# kulgurpowerMCU2.net
KiCad netlist of a schematic drawn in EAGLE
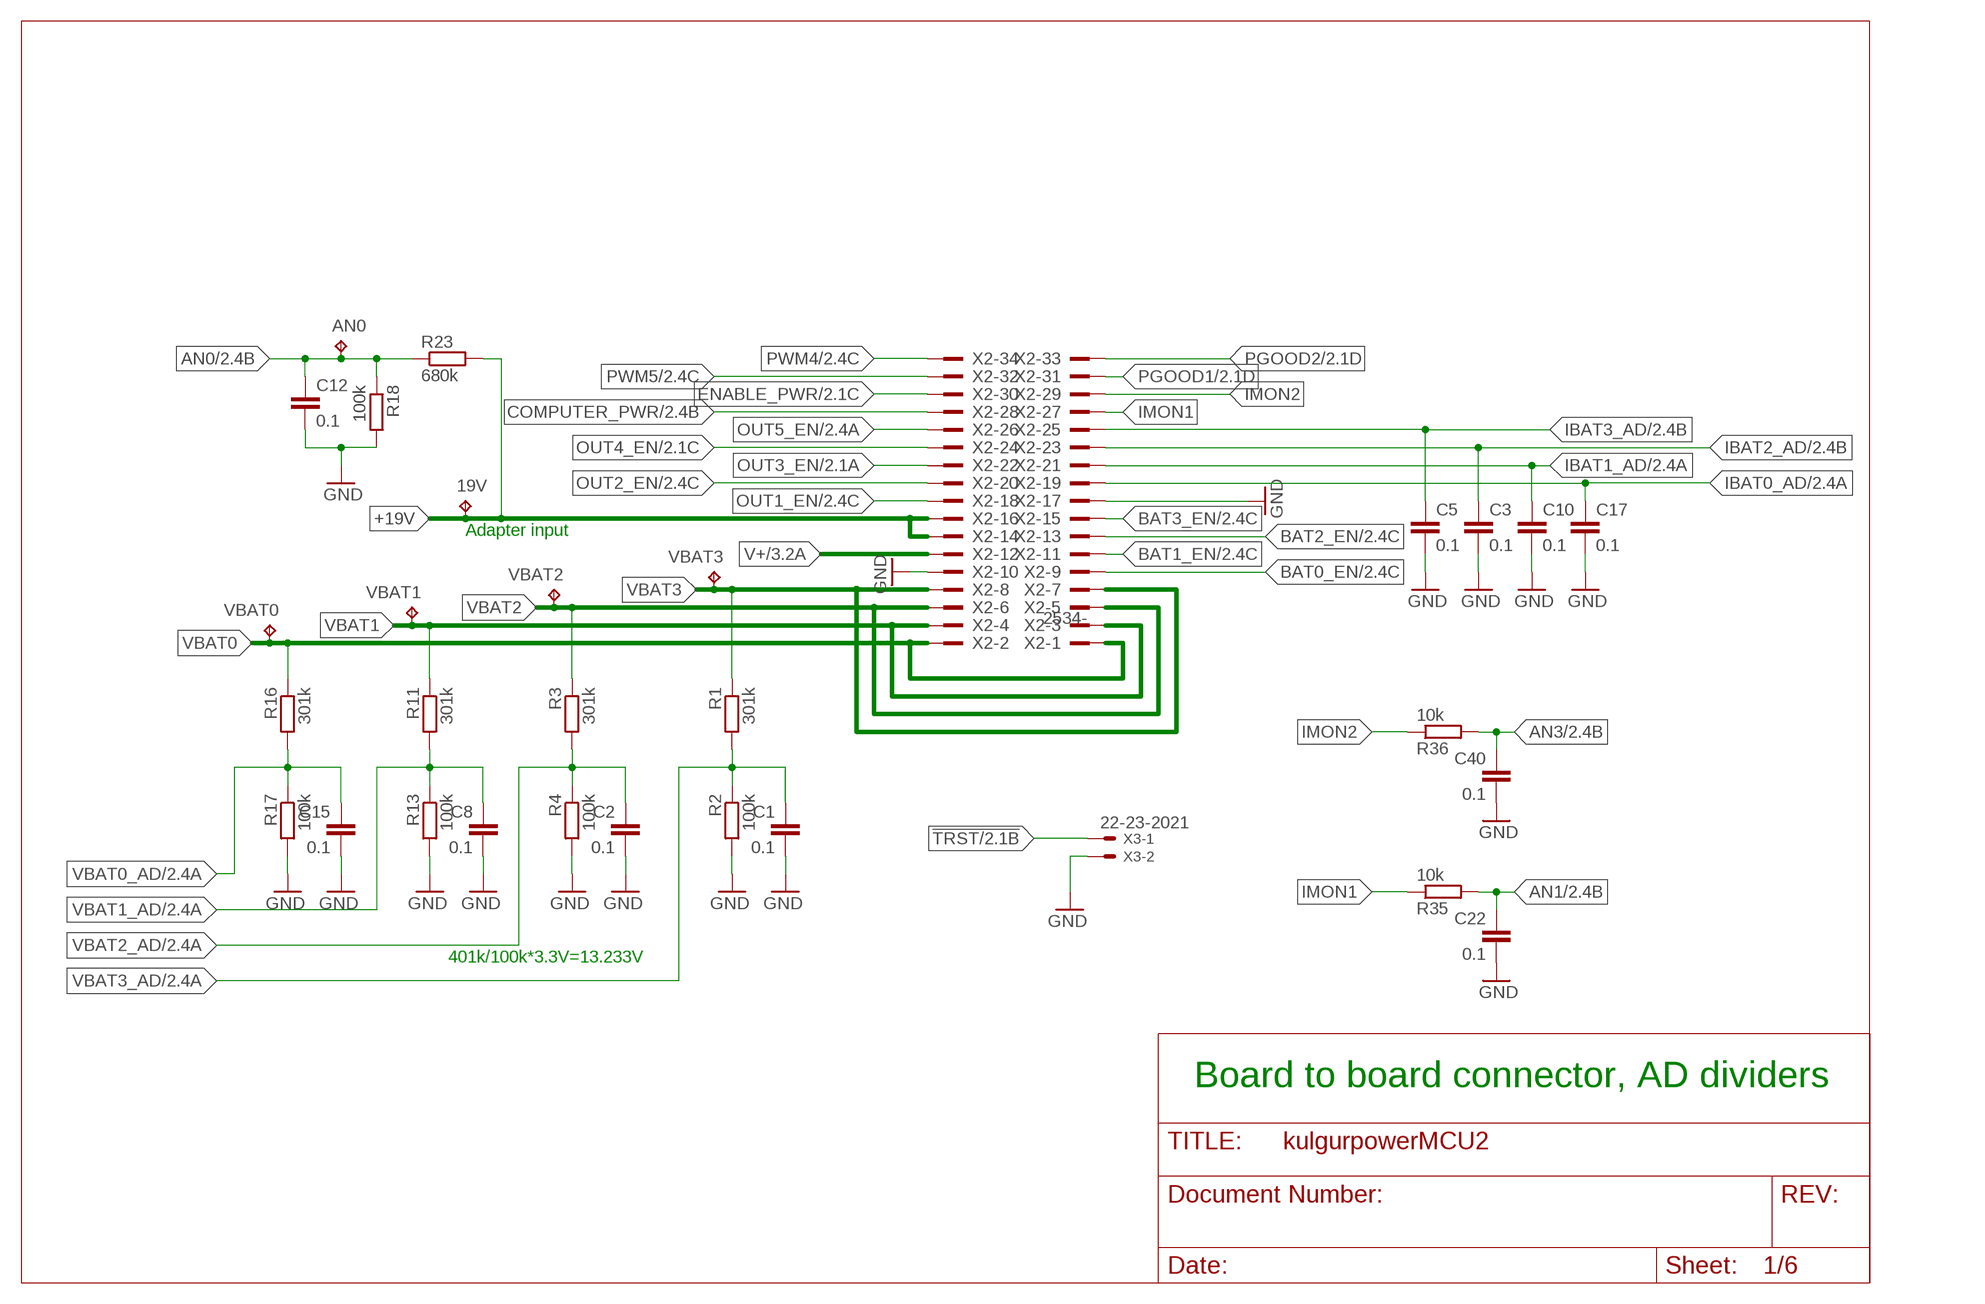
[diagram p0: schematic, sheet 1]
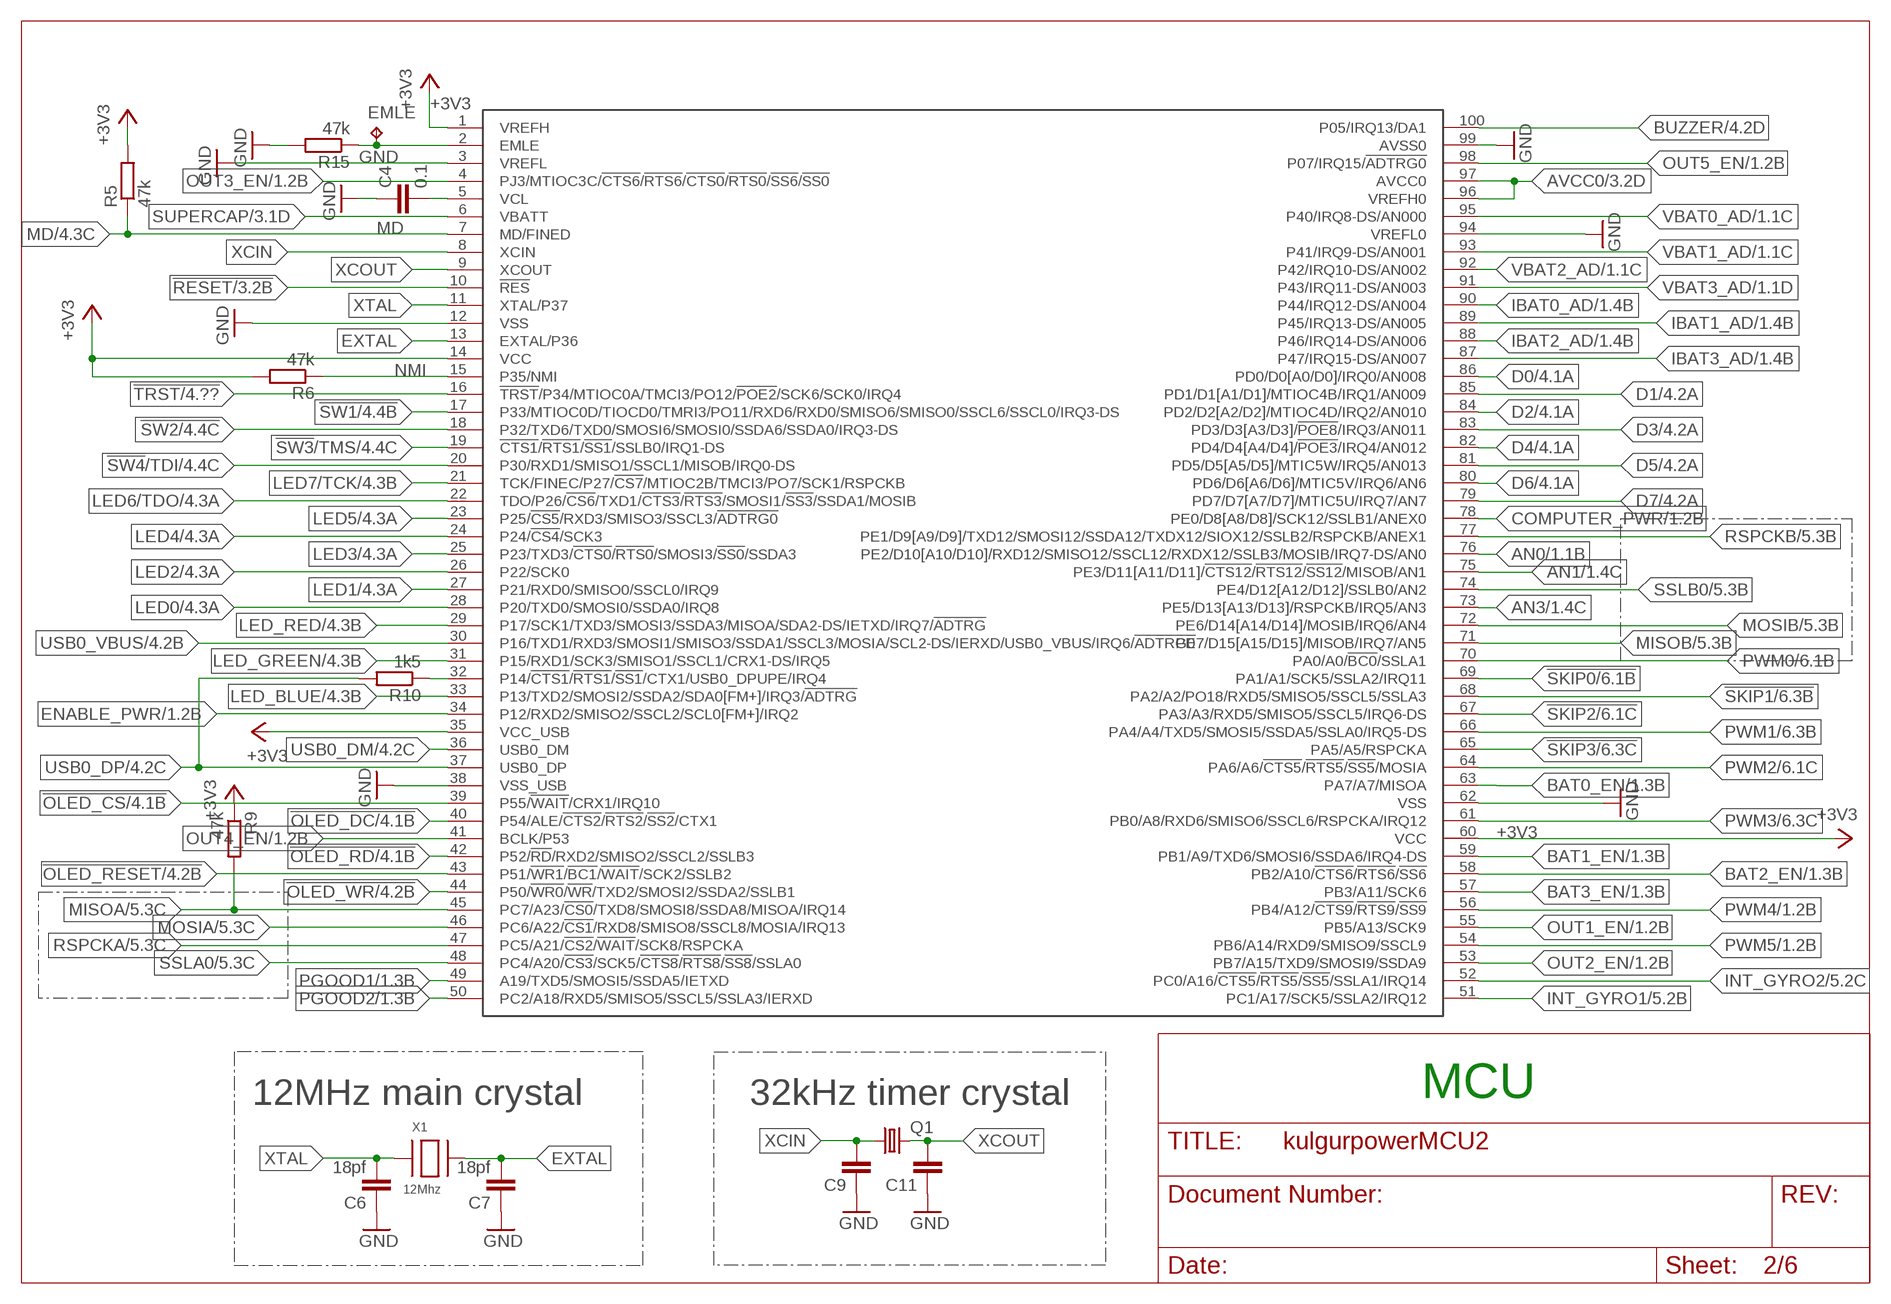
[diagram p1: schematic, sheet 2]
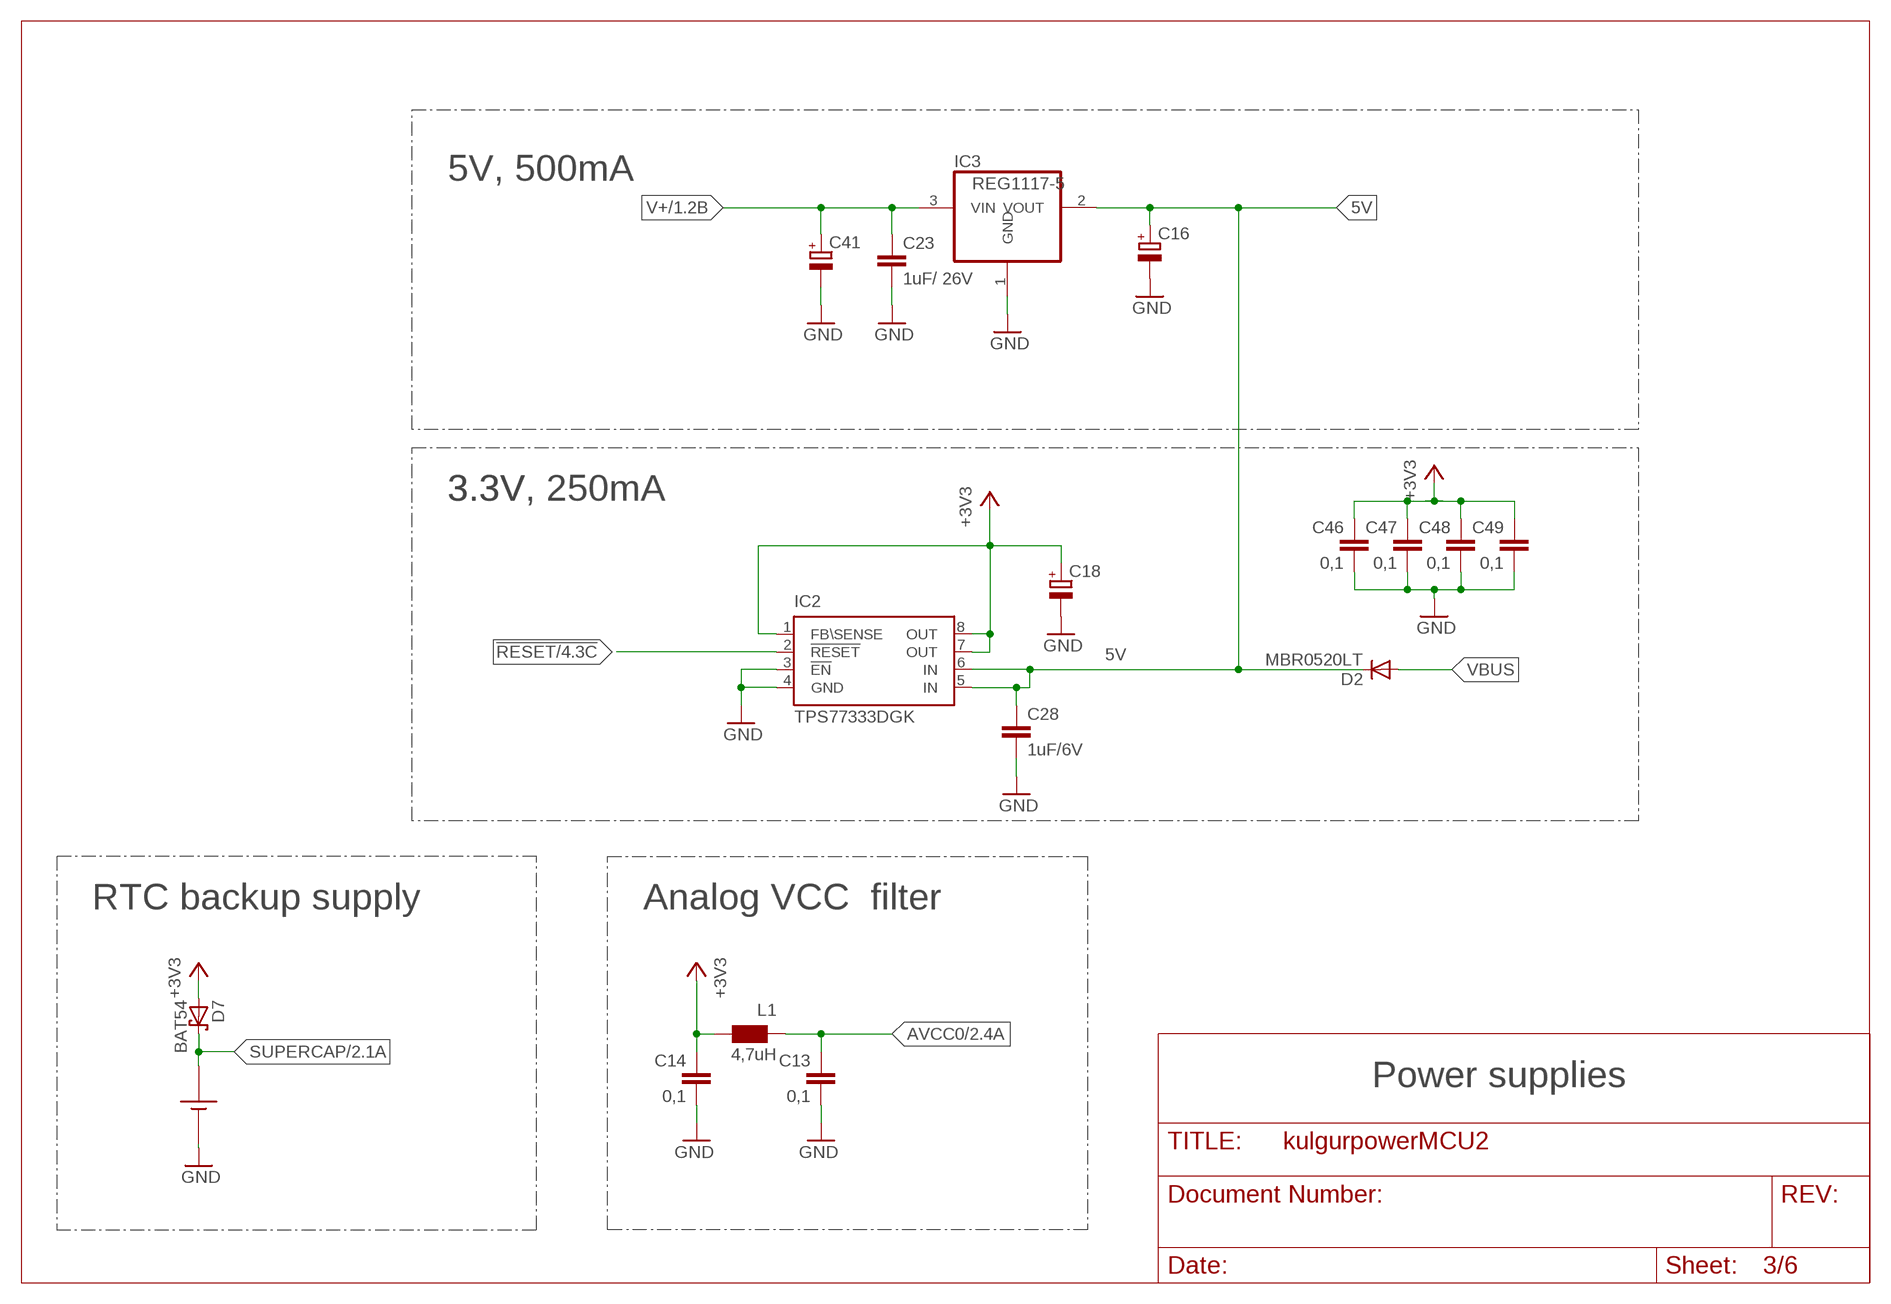
[diagram p2: schematic, sheet 3]
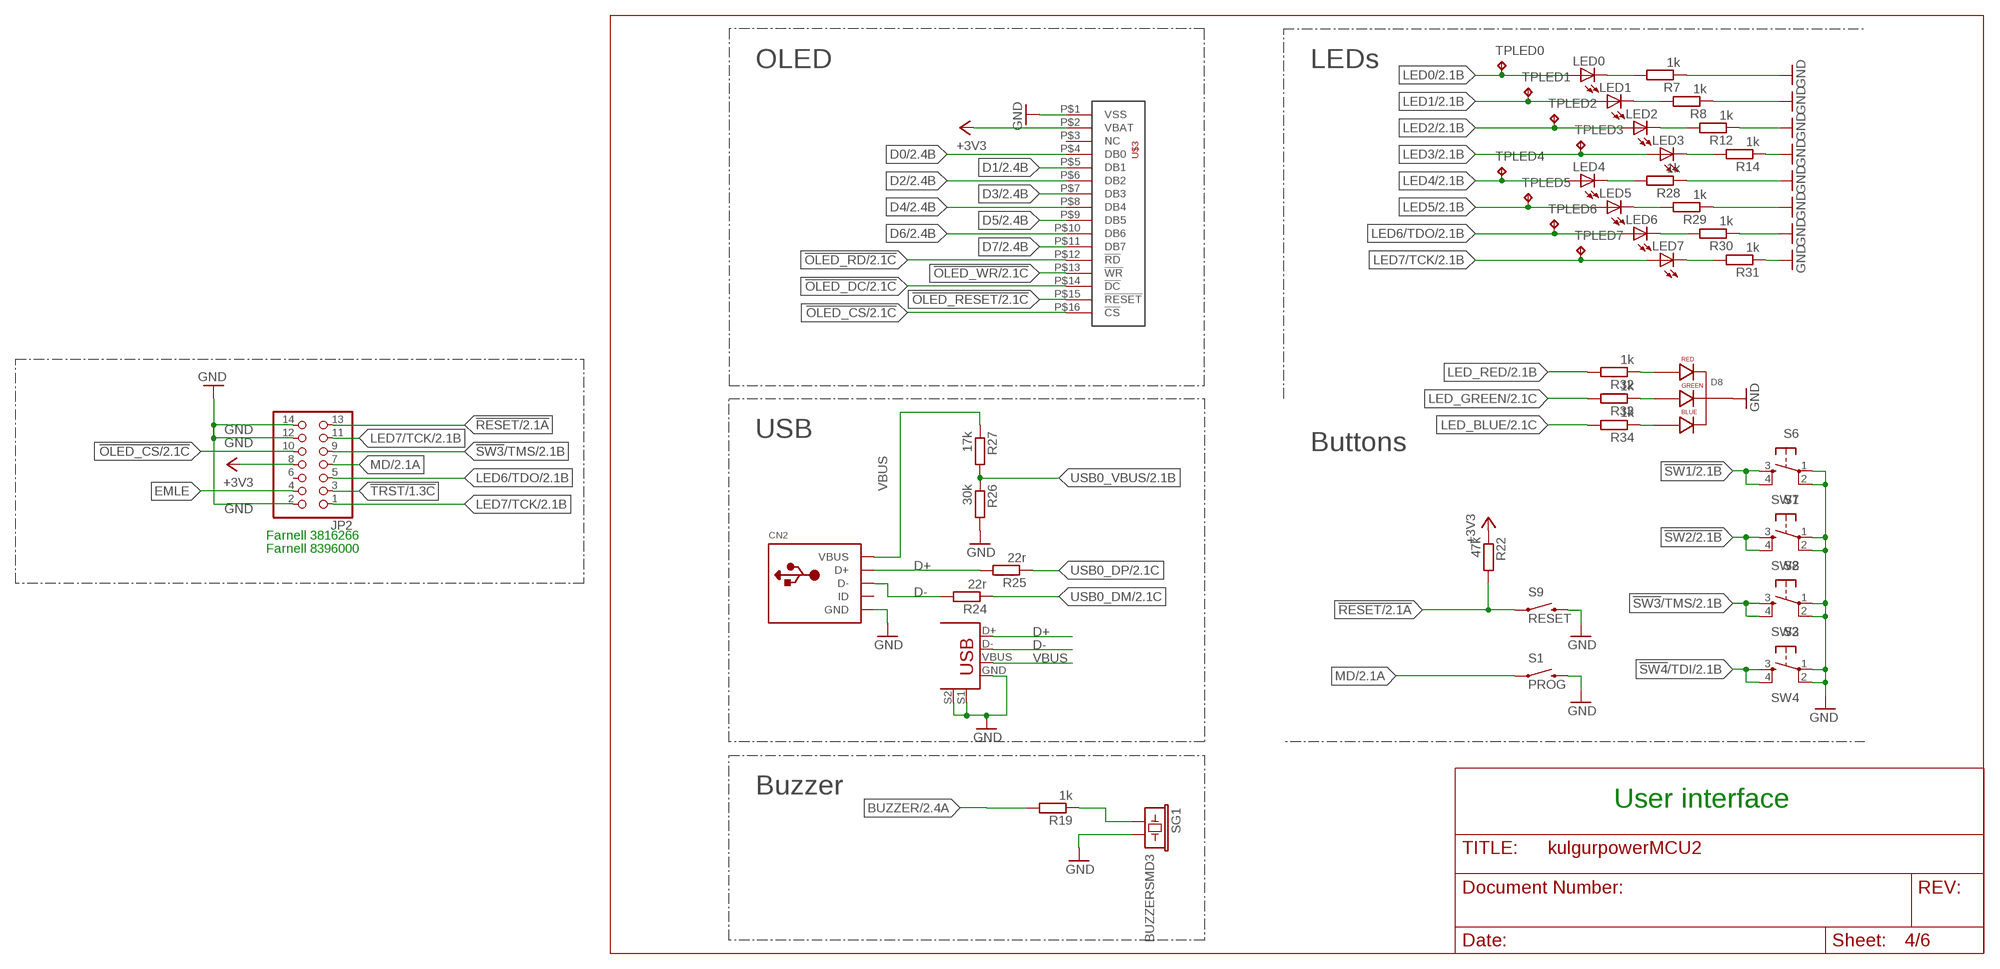
[diagram p3: schematic, sheet 4]
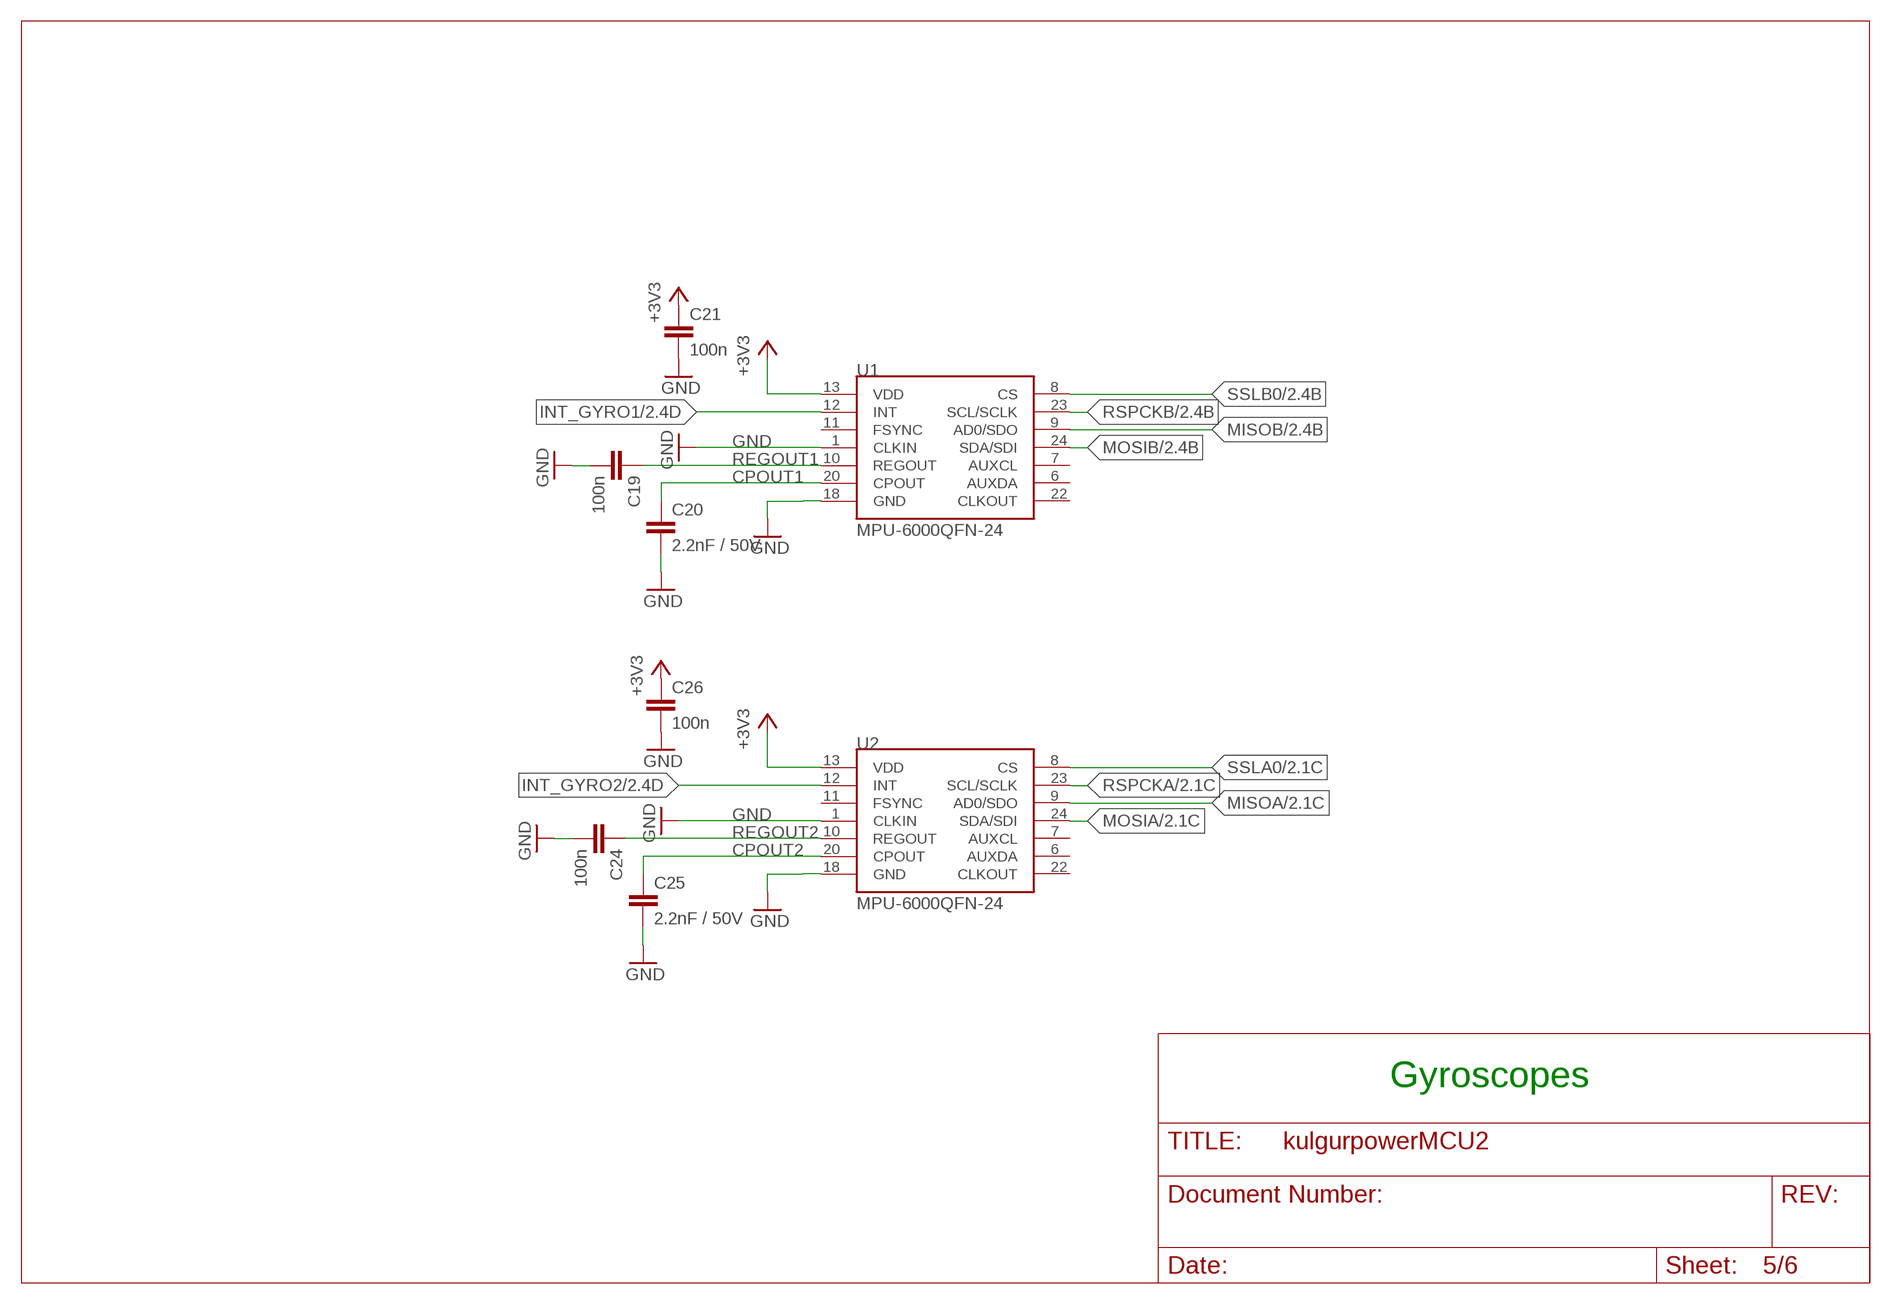
[diagram p4: schematic, sheet 5]
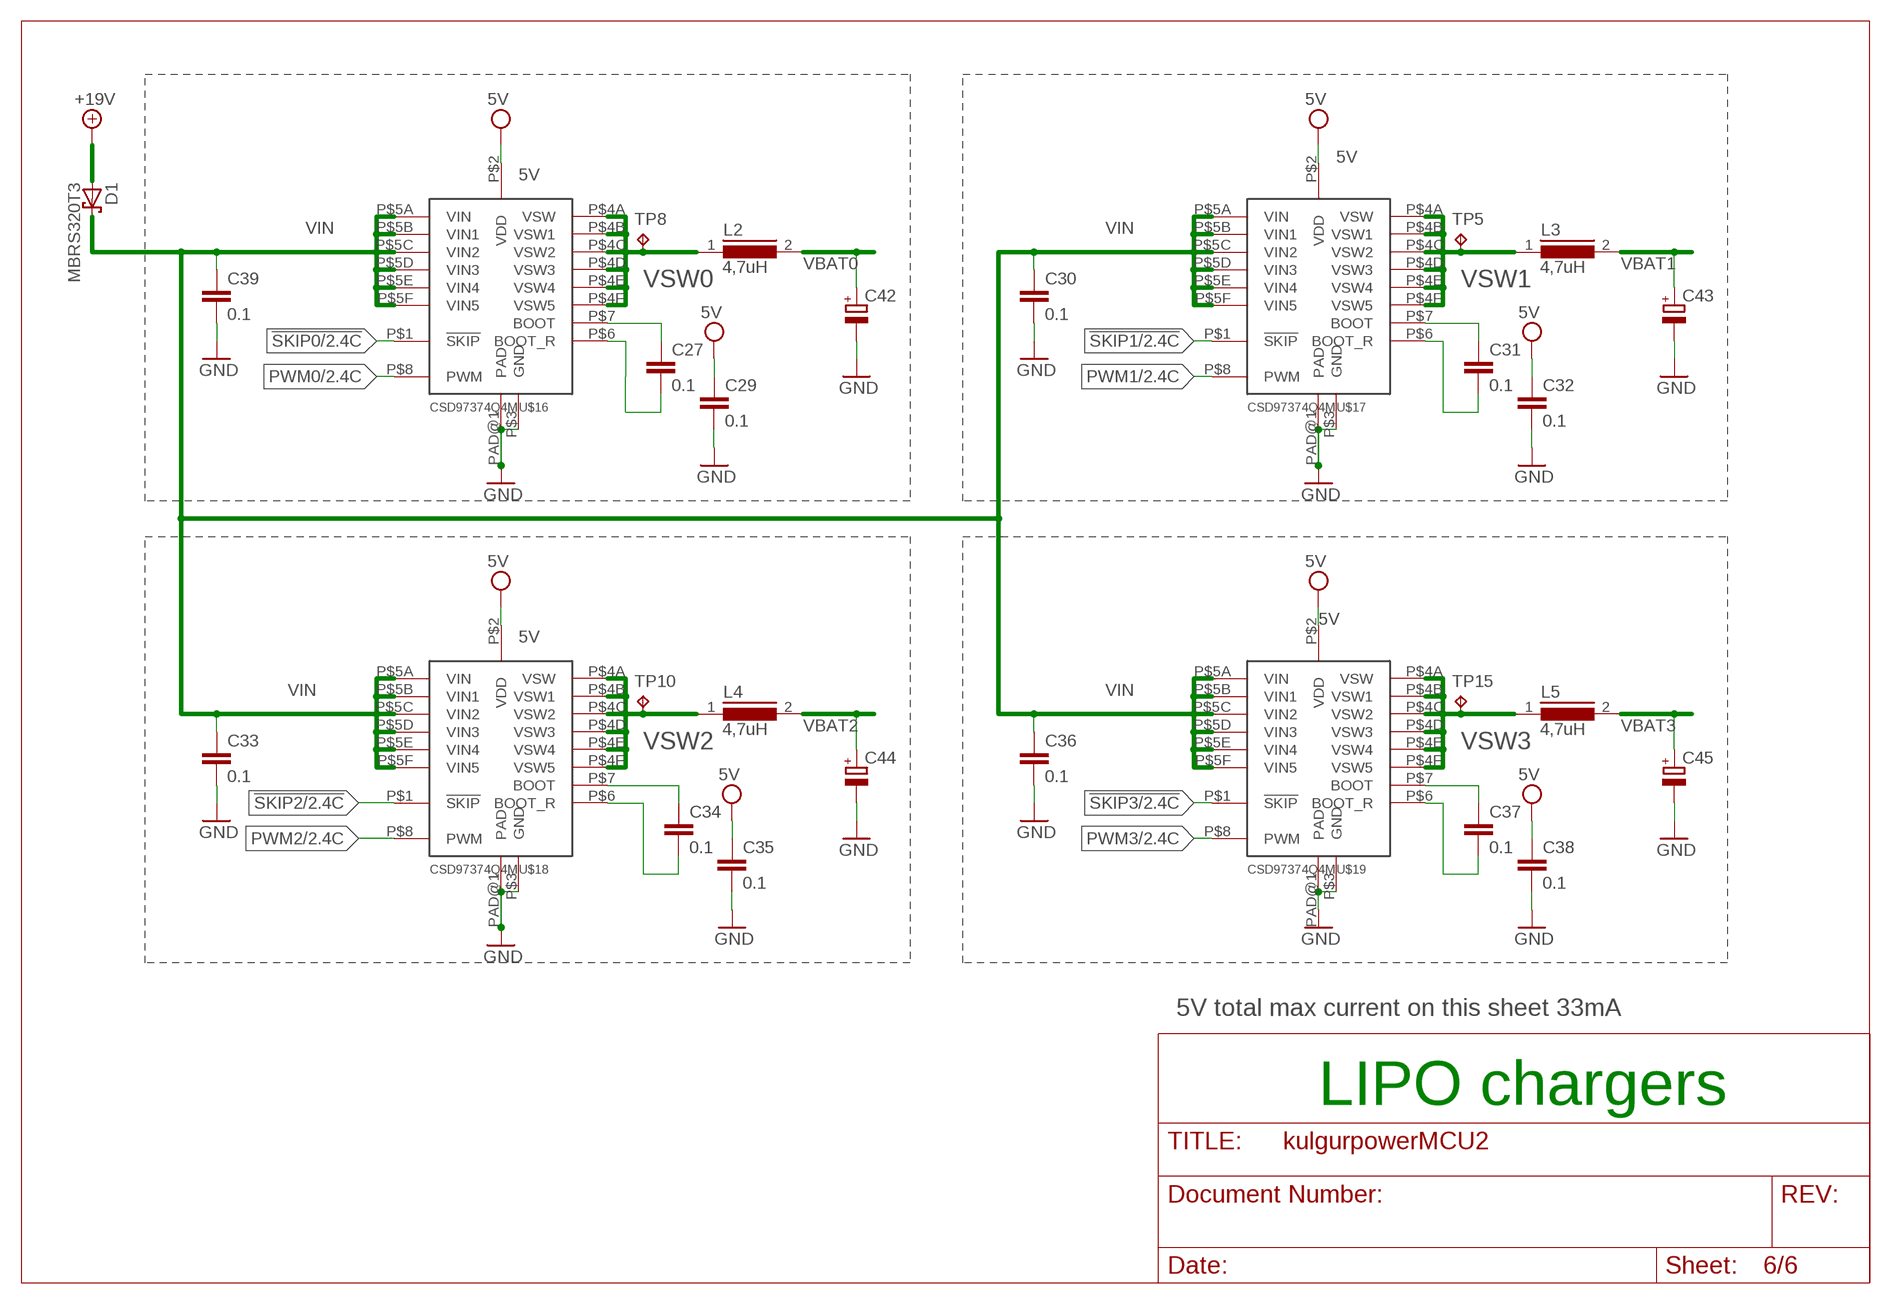
[diagram p5: schematic, sheet 6]

(export (version "E")
  (design (tool "Eeschema 10.0.6"))
  (components
    (comp (ref "C13")
      (value "0,1")
      (footprint "eagle-import:0603-CAP")
      (libsource (lib "eagle-import") (part "CAP0603-CAP"))
    )
    (comp (ref "C14")
      (value "0,1")
      (footprint "eagle-import:0603-CAP")
      (libsource (lib "eagle-import") (part "CAP0603-CAP"))
    )
    (comp (ref "C16")
      (value "CPOL-EUC/6032-28R")
      (footprint "eagle-import:C_6032-28R")
      (libsource (lib "eagle-import") (part "CPOL-EUC/6032-28R"))
    )
    (comp (ref "C18")
      (value "CPOL-EUC/6032-28R")
      (footprint "eagle-import:C_6032-28R")
      (libsource (lib "eagle-import") (part "CPOL-EUC/6032-28R"))
    )
    (comp (ref "C23")
      (value "1uF/ 26V")
      (footprint "eagle-import:C0805")
      (libsource (lib "eagle-import") (part "resistor_C-EUC0805"))
    )
    (comp (ref "C28")
      (value "1uF/6V")
      (footprint "eagle-import:C0603")
      (libsource (lib "eagle-import") (part "resistor_C-EUC0603"))
    )
    (comp (ref "C41")
      (value "CPOL-EUC/6032-28R")
      (footprint "eagle-import:C_6032-28R")
      (libsource (lib "eagle-import") (part "CPOL-EUC/6032-28R"))
    )
    (comp (ref "C46")
      (value "0,1")
      (footprint "eagle-import:0603-CAP")
      (libsource (lib "eagle-import") (part "CAP0603-CAP"))
    )
    (comp (ref "C47")
      (value "0,1")
      (footprint "eagle-import:0603-CAP")
      (libsource (lib "eagle-import") (part "CAP0603-CAP"))
    )
    (comp (ref "C48")
      (value "0,1")
      (footprint "eagle-import:0603-CAP")
      (libsource (lib "eagle-import") (part "CAP0603-CAP"))
    )
    (comp (ref "C49")
      (value "0,1")
      (footprint "eagle-import:0603-CAP")
      (libsource (lib "eagle-import") (part "CAP0603-CAP"))
    )
    (comp (ref "D2")
      (value "MBR0520LT")
      (footprint "eagle-import:SOD123")
      (libsource (lib "eagle-import") (part "MBR0520LT"))
    )
    (comp (ref "D7")
      (value "BAT54")
      (footprint "eagle-import:SOT23")
      (libsource (lib "eagle-import") (part "BAT54"))
    )
    (comp (ref "IC2")
      (value "TPS77333DGK")
      (footprint "eagle-import:MSOP8")
      (libsource (lib "eagle-import") (part "TPS773"))
    )
    (comp (ref "IC3")
      (value "REG1117-5")
      (footprint "eagle-import:SOT223")
      (fields (field (name "MPN") "REG1117"))
      (libsource (lib "eagle-import") (part "REG1117"))
    )
    (comp (ref "L1")
      (value "4,7uH")
      (footprint "eagle-import:WE-KI_0805_B")
      (libsource (lib "eagle-import") (part "WE-KIHQ_0805"))
    )
    (comp (ref "U$1")
      (value "EDLRD224V3R6C")
      (footprint "eagle-import:EDLRD224V3R6C")
      (libsource (lib "eagle-import") (part "EDLRD224V3R6C"))
    )
    (comp (ref "C19")
      (value "100n")
      (footprint "eagle-import:C0603")
      (libsource (lib "eagle-import") (part "C-EUC0603"))
    )
    (comp (ref "C20")
      (value "2.2nF / 50V")
      (footprint "eagle-import:C0402")
      (libsource (lib "eagle-import") (part "C0402"))
    )
    (comp (ref "C21")
      (value "100n")
      (footprint "eagle-import:C0603")
      (libsource (lib "eagle-import") (part "C-EUC0603"))
    )
    (comp (ref "C24")
      (value "100n")
      (footprint "eagle-import:C0603")
      (libsource (lib "eagle-import") (part "C-EUC0603"))
    )
    (comp (ref "C25")
      (value "2.2nF / 50V")
      (footprint "eagle-import:C0402")
      (libsource (lib "eagle-import") (part "C0402"))
    )
    (comp (ref "C26")
      (value "100n")
      (footprint "eagle-import:C0603")
      (libsource (lib "eagle-import") (part "C-EUC0603"))
    )
    (comp (ref "U1")
      (value "MPU-6000QFN-24")
      (footprint "eagle-import:QFN-24-TESTING")
      (libsource (lib "eagle-import") (part "MPU-6000QFN-24"))
    )
    (comp (ref "U2")
      (value "MPU-6000QFN-24")
      (footprint "eagle-import:QFN-24-TESTING")
      (libsource (lib "eagle-import") (part "MPU-6000QFN-24"))
    )
    (comp (ref "CN2")
      (value "USBMINIB")
      (footprint "eagle-import:USB-MINIB")
      (libsource (lib "eagle-import") (part "USBMINIB"))
    )
    (comp (ref "D8")
      (value "WP154A4SUREQBFZGW")
      (footprint "eagle-import:LED-RGB-THRU")
      (fields (field (name "PROD_ID") "DIO-09434"))
      (libsource (lib "eagle-import") (part "LED-RGB-CC-THRUDIFFUSE"))
    )
    (comp (ref "JP2")
      (value "PINHD-2X7")
      (footprint "eagle-import:2X07")
      (libsource (lib "eagle-import") (part "PINHD-2X7"))
    )
    (comp (ref "LED0")
      (value "LED0603")
      (footprint "eagle-import:LED-0603")
      (libsource (lib "eagle-import") (part "LED0603"))
    )
    (comp (ref "LED1")
      (value "LED0603")
      (footprint "eagle-import:LED-0603")
      (libsource (lib "eagle-import") (part "LED0603"))
    )
    (comp (ref "LED2")
      (value "LED0603")
      (footprint "eagle-import:LED-0603")
      (libsource (lib "eagle-import") (part "LED0603"))
    )
    (comp (ref "LED3")
      (value "LED0603")
      (footprint "eagle-import:LED-0603")
      (libsource (lib "eagle-import") (part "LED0603"))
    )
    (comp (ref "LED4")
      (value "LED0603")
      (footprint "eagle-import:LED-0603")
      (libsource (lib "eagle-import") (part "LED0603"))
    )
    (comp (ref "LED5")
      (value "LED0603")
      (footprint "eagle-import:LED-0603")
      (libsource (lib "eagle-import") (part "LED0603"))
    )
    (comp (ref "LED6")
      (value "LED0603")
      (footprint "eagle-import:LED-0603")
      (libsource (lib "eagle-import") (part "LED0603"))
    )
    (comp (ref "LED7")
      (value "LED0603")
      (footprint "eagle-import:LED-0603")
      (libsource (lib "eagle-import") (part "LED0603"))
    )
    (comp (ref "R7")
      (value "1k")
      (footprint "eagle-import:R0603")
      (libsource (lib "eagle-import") (part "R-EU_R0603"))
    )
    (comp (ref "R8")
      (value "1k")
      (footprint "eagle-import:R0603")
      (libsource (lib "eagle-import") (part "R-EU_R0603"))
    )
    (comp (ref "R12")
      (value "1k")
      (footprint "eagle-import:R0603")
      (libsource (lib "eagle-import") (part "R-EU_R0603"))
    )
    (comp (ref "R14")
      (value "1k")
      (footprint "eagle-import:R0603")
      (libsource (lib "eagle-import") (part "R-EU_R0603"))
    )
    (comp (ref "R19")
      (value "1k")
      (footprint "eagle-import:R0603")
      (libsource (lib "eagle-import") (part "R-EU_R0603"))
    )
    (comp (ref "R22")
      (value "47k")
      (footprint "eagle-import:R0603")
      (libsource (lib "eagle-import") (part "R-EU_R0603"))
    )
    (comp (ref "R24")
      (value "22r")
      (footprint "eagle-import:R0603")
      (libsource (lib "eagle-import") (part "R-EU_R0603"))
    )
    (comp (ref "R25")
      (value "22r")
      (footprint "eagle-import:R0603")
      (libsource (lib "eagle-import") (part "R-EU_R0603"))
    )
    (comp (ref "R26")
      (value "30k")
      (footprint "eagle-import:R0603")
      (libsource (lib "eagle-import") (part "R-EU_R0603"))
    )
    (comp (ref "R27")
      (value "17k")
      (footprint "eagle-import:R0603")
      (libsource (lib "eagle-import") (part "R-EU_R0603"))
    )
    (comp (ref "R28")
      (value "1k")
      (footprint "eagle-import:R0603")
      (libsource (lib "eagle-import") (part "R-EU_R0603"))
    )
    (comp (ref "R29")
      (value "1k")
      (footprint "eagle-import:R0603")
      (libsource (lib "eagle-import") (part "R-EU_R0603"))
    )
    (comp (ref "R30")
      (value "1k")
      (footprint "eagle-import:R0603")
      (libsource (lib "eagle-import") (part "R-EU_R0603"))
    )
    (comp (ref "R31")
      (value "1k")
      (footprint "eagle-import:R0603")
      (libsource (lib "eagle-import") (part "R-EU_R0603"))
    )
    (comp (ref "R32")
      (value "1k")
      (footprint "eagle-import:R0603")
      (libsource (lib "eagle-import") (part "R-EU_R0603"))
    )
    (comp (ref "R33")
      (value "1k")
      (footprint "eagle-import:R0603")
      (libsource (lib "eagle-import") (part "R-EU_R0603"))
    )
    (comp (ref "R34")
      (value "1k")
      (footprint "eagle-import:R0603")
      (libsource (lib "eagle-import") (part "R-EU_R0603"))
    )
    (comp (ref "S1")
      (value "PROG")
      (footprint "eagle-import:TACTILE-PTH-SIDEEZ")
      (libsource (lib "eagle-import") (part "SWITCH-MOMENTARY-2SIDE_EZ"))
    )
    (comp (ref "S2")
      (value "SW4")
      (footprint "eagle-import:TACTILE_SWITCH_SMD")
      (fields (field (name "PROD_ID") "SWCH-08247"))
      (libsource (lib "eagle-import") (part "TAC_SWITCHSMD"))
    )
    (comp (ref "S6")
      (value "SW1")
      (footprint "eagle-import:TACTILE_SWITCH_SMD")
      (libsource (lib "eagle-import") (part "TAC_SWITCHSMD"))
    )
    (comp (ref "S7")
      (value "SW2")
      (footprint "eagle-import:TACTILE_SWITCH_SMD")
      (libsource (lib "eagle-import") (part "TAC_SWITCHSMD"))
    )
    (comp (ref "S8")
      (value "SW3")
      (footprint "eagle-import:TACTILE_SWITCH_SMD")
      (libsource (lib "eagle-import") (part "TAC_SWITCHSMD"))
    )
    (comp (ref "S9")
      (value "RESET")
      (footprint "eagle-import:TACTILE-PTH-SIDEEZ")
      (libsource (lib "eagle-import") (part "SWITCH-MOMENTARY-2SIDE_EZ"))
    )
    (comp (ref "SG1")
      (value "BUZZERSMD3")
      (footprint "eagle-import:BUZZER-CMT1102")
      (libsource (lib "eagle-import") (part "BUZZERSMD3"))
    )
    (comp (ref "TPLED0")
      (value "LED0")
      (footprint "eagle-import:B1,27")
      (libsource (lib "eagle-import") (part "TPB1,27"))
    )
    (comp (ref "TPLED1")
      (value "LED0")
      (footprint "eagle-import:B1,27")
      (libsource (lib "eagle-import") (part "TPB1,27"))
    )
    (comp (ref "TPLED2")
      (value "LED0")
      (footprint "eagle-import:B1,27")
      (libsource (lib "eagle-import") (part "TPB1,27"))
    )
    (comp (ref "TPLED3")
      (value "LED0")
      (footprint "eagle-import:B1,27")
      (libsource (lib "eagle-import") (part "TPB1,27"))
    )
    (comp (ref "TPLED4")
      (value "LED0")
      (footprint "eagle-import:B1,27")
      (libsource (lib "eagle-import") (part "TPB1,27"))
    )
    (comp (ref "TPLED5")
      (value "LED0")
      (footprint "eagle-import:B1,27")
      (libsource (lib "eagle-import") (part "TPB1,27"))
    )
    (comp (ref "TPLED6")
      (value "LED0")
      (footprint "eagle-import:B1,27")
      (libsource (lib "eagle-import") (part "TPB1,27"))
    )
    (comp (ref "TPLED7")
      (value "LED0")
      (footprint "eagle-import:B1,27")
      (libsource (lib "eagle-import") (part "TPB1,27"))
    )
    (comp (ref "U$2")
      (value "USB+SHIELD")
      (footprint "eagle-import:USB-B-PTH")
      (libsource (lib "eagle-import") (part "USB+SHIELD"))
    )
    (comp (ref "U$3")
      (value "ER-OLEDM032-1")
      (footprint "eagle-import:ER-OLEDM032-1")
      (libsource (lib "eagle-import") (part "ER-OLEDM032-1"))
    )
    (comp (ref "19V")
      (value "TPB1,27")
      (footprint "eagle-import:B1,27")
      (libsource (lib "eagle-import") (part "TPB1,27"))
    )
    (comp (ref "AN0")
      (value "TPB1,27")
      (footprint "eagle-import:B1,27")
      (libsource (lib "eagle-import") (part "TPB1,27"))
    )
    (comp (ref "C1")
      (value "0.1")
      (footprint "eagle-import:C0603")
      (libsource (lib "eagle-import") (part "C-EUC0603"))
    )
    (comp (ref "C2")
      (value "0.1")
      (footprint "eagle-import:C0603")
      (libsource (lib "eagle-import") (part "C-EUC0603"))
    )
    (comp (ref "C3")
      (value "0.1")
      (footprint "eagle-import:C0603")
      (libsource (lib "eagle-import") (part "C-EUC0603"))
    )
    (comp (ref "C5")
      (value "0.1")
      (footprint "eagle-import:C0603")
      (libsource (lib "eagle-import") (part "C-EUC0603"))
    )
    (comp (ref "C8")
      (value "0.1")
      (footprint "eagle-import:C0603")
      (libsource (lib "eagle-import") (part "C-EUC0603"))
    )
    (comp (ref "C10")
      (value "0.1")
      (footprint "eagle-import:C0603")
      (libsource (lib "eagle-import") (part "C-EUC0603"))
    )
    (comp (ref "C12")
      (value "0.1")
      (footprint "eagle-import:0603-CAP")
      (libsource (lib "eagle-import") (part "CAP0603-CAP"))
    )
    (comp (ref "C15")
      (value "0.1")
      (footprint "eagle-import:C0603")
      (libsource (lib "eagle-import") (part "C-EUC0603"))
    )
    (comp (ref "C17")
      (value "0.1")
      (footprint "eagle-import:C0603")
      (libsource (lib "eagle-import") (part "C-EUC0603"))
    )
    (comp (ref "C22")
      (value "0.1")
      (footprint "eagle-import:C0603")
      (libsource (lib "eagle-import") (part "C-EUC0603"))
    )
    (comp (ref "C40")
      (value "0.1")
      (footprint "eagle-import:C0603")
      (libsource (lib "eagle-import") (part "C-EUC0603"))
    )
    (comp (ref "R1")
      (value "301k")
      (footprint "eagle-import:R0603")
      (libsource (lib "eagle-import") (part "R-EU_R0603"))
    )
    (comp (ref "R2")
      (value "100k")
      (footprint "eagle-import:R0603")
      (libsource (lib "eagle-import") (part "R-EU_R0603"))
    )
    (comp (ref "R3")
      (value "301k")
      (footprint "eagle-import:R0603")
      (libsource (lib "eagle-import") (part "R-EU_R0603"))
    )
    (comp (ref "R4")
      (value "100k")
      (footprint "eagle-import:R0603")
      (libsource (lib "eagle-import") (part "R-EU_R0603"))
    )
    (comp (ref "R11")
      (value "301k")
      (footprint "eagle-import:R0603")
      (libsource (lib "eagle-import") (part "R-EU_R0603"))
    )
    (comp (ref "R13")
      (value "100k")
      (footprint "eagle-import:R0603")
      (libsource (lib "eagle-import") (part "R-EU_R0603"))
    )
    (comp (ref "R16")
      (value "301k")
      (footprint "eagle-import:R0603")
      (libsource (lib "eagle-import") (part "R-EU_R0603"))
    )
    (comp (ref "R17")
      (value "100k")
      (footprint "eagle-import:R0603")
      (libsource (lib "eagle-import") (part "R-EU_R0603"))
    )
    (comp (ref "R18")
      (value "100k")
      (footprint "eagle-import:R0603")
      (libsource (lib "eagle-import") (part "R-EU_R0603"))
    )
    (comp (ref "R23")
      (value "680k")
      (footprint "eagle-import:R0603")
      (libsource (lib "eagle-import") (part "R-EU_R0603"))
    )
    (comp (ref "R35")
      (value "10k")
      (footprint "eagle-import:R0603")
      (libsource (lib "eagle-import") (part "R-EU_R0603"))
    )
    (comp (ref "R36")
      (value "10k")
      (footprint "eagle-import:R0603")
      (libsource (lib "eagle-import") (part "R-EU_R0603"))
    )
    (comp (ref "VBAT0")
      (value "TPB1,27")
      (footprint "eagle-import:B1,27")
      (libsource (lib "eagle-import") (part "TPB1,27"))
    )
    (comp (ref "VBAT1")
      (value "TPB1,27")
      (footprint "eagle-import:B1,27")
      (libsource (lib "eagle-import") (part "TPB1,27"))
    )
    (comp (ref "VBAT2")
      (value "TPB1,27")
      (footprint "eagle-import:B1,27")
      (libsource (lib "eagle-import") (part "TPB1,27"))
    )
    (comp (ref "VBAT3")
      (value "TPB1,27")
      (footprint "eagle-import:B1,27")
      (libsource (lib "eagle-import") (part "TPB1,27"))
    )
    (comp (ref "X2")
      (value "2534-")
      (footprint "eagle-import:PAK100_2500-34")
      (libsource (lib "eagle-import") (part "2534-"))
    )
    (comp (ref "X3")
      (value "22-23-2021")
      (footprint "eagle-import:22-23-2021")
      (fields (field (name "MF") "MOLEX"))
      (libsource (lib "eagle-import") (part "22-23-2021"))
    )
    (comp (ref "C4")
      (value "0.1")
      (footprint "eagle-import:0603-CAP")
      (libsource (lib "eagle-import") (part "CAP0603-CAP"))
    )
    (comp (ref "C6")
      (value "18pf")
      (footprint "eagle-import:0603-CAP")
      (libsource (lib "eagle-import") (part "CAP0603-CAP"))
    )
    (comp (ref "C7")
      (value "18pf")
      (footprint "eagle-import:0603-CAP")
      (libsource (lib "eagle-import") (part "CAP0603-CAP"))
    )
    (comp (ref "C9")
      (value "CAP0603-CAP")
      (footprint "eagle-import:0603-CAP")
      (libsource (lib "eagle-import") (part "CAP0603-CAP"))
    )
    (comp (ref "C11")
      (value "CAP0603-CAP")
      (footprint "eagle-import:0603-CAP")
      (libsource (lib "eagle-import") (part "CAP0603-CAP"))
    )
    (comp (ref "EMLE")
      (value "TPB1,27")
      (footprint "eagle-import:B1,27")
      (libsource (lib "eagle-import") (part "TPB1,27"))
    )
    (comp (ref "Q1")
      (value "CRYSTALMM20SS")
      (footprint "eagle-import:MM20SS")
      (libsource (lib "eagle-import") (part "CRYSTALMM20SS"))
    )
    (comp (ref "R5")
      (value "47k")
      (footprint "eagle-import:R0603")
      (libsource (lib "eagle-import") (part "R-EU_R0603"))
    )
    (comp (ref "R6")
      (value "47k")
      (footprint "eagle-import:R0603")
      (libsource (lib "eagle-import") (part "R-EU_R0603"))
    )
    (comp (ref "R9")
      (value "47k")
      (footprint "eagle-import:R0603")
      (libsource (lib "eagle-import") (part "R-EU_R0603"))
    )
    (comp (ref "R10")
      (value "1k5")
      (footprint "eagle-import:R0603")
      (libsource (lib "eagle-import") (part "R-EU_R0603"))
    )
    (comp (ref "R15")
      (value "47k")
      (footprint "eagle-import:R0603")
      (libsource (lib "eagle-import") (part "R-EU_R0603"))
    )
    (comp (ref "U$14")
      (value "R5F5630ADDFP")
      (footprint "eagle-import:LTQFP100")
      (libsource (lib "eagle-import") (part "R5F5630ADDFP"))
    )
    (comp (ref "X1")
      (value "12Mhz")
      (footprint "eagle-import:NX5032")
      (libsource (lib "eagle-import") (part "XTALNX5032"))
    )
    (comp (ref "C27")
      (value "0.1")
      (footprint "eagle-import:C0603")
      (libsource (lib "eagle-import") (part "C-EUC0603"))
    )
    (comp (ref "C29")
      (value "0.1")
      (footprint "eagle-import:C0603")
      (libsource (lib "eagle-import") (part "C-EUC0603"))
    )
    (comp (ref "C30")
      (value "0.1")
      (footprint "eagle-import:C0603")
      (libsource (lib "eagle-import") (part "C-EUC0603"))
    )
    (comp (ref "C31")
      (value "0.1")
      (footprint "eagle-import:C0603")
      (libsource (lib "eagle-import") (part "C-EUC0603"))
    )
    (comp (ref "C32")
      (value "0.1")
      (footprint "eagle-import:C0603")
      (libsource (lib "eagle-import") (part "C-EUC0603"))
    )
    (comp (ref "C33")
      (value "0.1")
      (footprint "eagle-import:C0603")
      (libsource (lib "eagle-import") (part "C-EUC0603"))
    )
    (comp (ref "C34")
      (value "0.1")
      (footprint "eagle-import:C0603")
      (libsource (lib "eagle-import") (part "C-EUC0603"))
    )
    (comp (ref "C35")
      (value "0.1")
      (footprint "eagle-import:C0603")
      (libsource (lib "eagle-import") (part "C-EUC0603"))
    )
    (comp (ref "C36")
      (value "0.1")
      (footprint "eagle-import:C0603")
      (libsource (lib "eagle-import") (part "C-EUC0603"))
    )
    (comp (ref "C37")
      (value "0.1")
      (footprint "eagle-import:C0603")
      (libsource (lib "eagle-import") (part "C-EUC0603"))
    )
    (comp (ref "C38")
      (value "0.1")
      (footprint "eagle-import:C0603")
      (libsource (lib "eagle-import") (part "C-EUC0603"))
    )
    (comp (ref "C39")
      (value "0.1")
      (footprint "eagle-import:C0603")
      (libsource (lib "eagle-import") (part "C-EUC0603"))
    )
    (comp (ref "C42")
      (value "CPOL-EUC/6032-28R")
      (footprint "eagle-import:C_6032-28R")
      (libsource (lib "eagle-import") (part "CPOL-EUC/6032-28R"))
    )
    (comp (ref "C43")
      (value "CPOL-EUC/6032-28R")
      (footprint "eagle-import:C_6032-28R")
      (libsource (lib "eagle-import") (part "CPOL-EUC/6032-28R"))
    )
    (comp (ref "C44")
      (value "CPOL-EUC/6032-28R")
      (footprint "eagle-import:C_6032-28R")
      (libsource (lib "eagle-import") (part "CPOL-EUC/6032-28R"))
    )
    (comp (ref "C45")
      (value "CPOL-EUC/6032-28R")
      (footprint "eagle-import:C_6032-28R")
      (libsource (lib "eagle-import") (part "CPOL-EUC/6032-28R"))
    )
    (comp (ref "D1")
      (value "MBRS320T3")
      (footprint "eagle-import:SMC")
      (libsource (lib "eagle-import") (part "MBRS30T32"))
    )
    (comp (ref "L2")
      (value "4,7uH")
      (footprint "eagle-import:DR73")
      (libsource (lib "eagle-import") (part "DR73"))
    )
    (comp (ref "L3")
      (value "4,7uH")
      (footprint "eagle-import:DR73")
      (libsource (lib "eagle-import") (part "DR73"))
    )
    (comp (ref "L4")
      (value "4,7uH")
      (footprint "eagle-import:DR73")
      (libsource (lib "eagle-import") (part "DR73"))
    )
    (comp (ref "L5")
      (value "4,7uH")
      (footprint "eagle-import:DR73")
      (libsource (lib "eagle-import") (part "DR73"))
    )
    (comp (ref "TP5")
      (value "TPB2,54")
      (footprint "eagle-import:B2,54")
      (libsource (lib "eagle-import") (part "TPB2,54"))
    )
    (comp (ref "TP8")
      (value "TPB2,54")
      (footprint "eagle-import:B2,54")
      (libsource (lib "eagle-import") (part "TPB2,54"))
    )
    (comp (ref "TP10")
      (value "TPB2,54")
      (footprint "eagle-import:B2,54")
      (libsource (lib "eagle-import") (part "TPB2,54"))
    )
    (comp (ref "TP15")
      (value "TPB2,54")
      (footprint "eagle-import:B2,54")
      (libsource (lib "eagle-import") (part "TPB2,54"))
    )
    (comp (ref "U$16")
      (value "CSD97374Q4M")
      (footprint "eagle-import:CSD97374Q4M")
      (libsource (lib "eagle-import") (part "CSD97374Q4M"))
    )
    (comp (ref "U$17")
      (value "CSD97374Q4M")
      (footprint "eagle-import:CSD97374Q4M")
      (libsource (lib "eagle-import") (part "CSD97374Q4M"))
    )
    (comp (ref "U$18")
      (value "CSD97374Q4M")
      (footprint "eagle-import:CSD97374Q4M")
      (libsource (lib "eagle-import") (part "CSD97374Q4M"))
    )
    (comp (ref "U$19")
      (value "CSD97374Q4M")
      (footprint "eagle-import:CSD97374Q4M")
      (libsource (lib "eagle-import") (part "CSD97374Q4M"))
    )
  )
  (nets
    (net (code "1") (name "+3V3") (class "Default")
      (node (ref "C14") (pin "1") (pinfunction "1_1") (pintype "passive"))
      (node (ref "C18") (pin "+") (pinfunction "+_+") (pintype "passive"))
      (node (ref "C21") (pin "1") (pinfunction "1_1") (pintype "passive"))
      (node (ref "C26") (pin "1") (pinfunction "1_1") (pintype "passive"))
      (node (ref "C46") (pin "1") (pinfunction "1_1") (pintype "passive"))
      (node (ref "C47") (pin "1") (pinfunction "1_1") (pintype "passive"))
      (node (ref "C48") (pin "1") (pinfunction "1_1") (pintype "passive"))
      (node (ref "C49") (pin "1") (pinfunction "1_1") (pintype "passive"))
      (node (ref "D7") (pin "1") (pinfunction "A_1") (pintype "passive"))
      (node (ref "IC2") (pin "1") (pinfunction "FB\\SENSE_1") (pintype "input"))
      (node (ref "IC2") (pin "7") (pinfunction "OUT_7") (pintype "output"))
      (node (ref "IC2") (pin "8") (pinfunction "OUT_8") (pintype "passive"))
      (node (ref "JP2") (pin "8") (pinfunction "8_8") (pintype "passive"))
      (node (ref "L1") (pin "1") (pinfunction "2_1") (pintype "passive"))
      (node (ref "R22") (pin "1") (pinfunction "1_1") (pintype "passive"))
      (node (ref "R5") (pin "2") (pinfunction "2_2") (pintype "passive"))
      (node (ref "R6") (pin "2") (pinfunction "2_2") (pintype "passive"))
      (node (ref "R9") (pin "1") (pinfunction "1_1") (pintype "passive"))
      (node (ref "U$14") (pin "1") (pinfunction "VREFH_1") (pintype "bidirectional"))
      (node (ref "U$14") (pin "14") (pinfunction "VCC_14") (pintype "bidirectional"))
      (node (ref "U$14") (pin "35") (pinfunction "VCC_USB_35") (pintype "bidirectional"))
      (node (ref "U$14") (pin "60") (pinfunction "VCC_60") (pintype "bidirectional"))
      (node (ref "U$3") (pin "P$2") (pinfunction "VBAT_P$2") (pintype "bidirectional"))
      (node (ref "U1") (pin "13") (pinfunction "VDD_13") (pintype "bidirectional"))
      (node (ref "U2") (pin "13") (pinfunction "VDD_13") (pintype "bidirectional"))
    )
    (net (code "2") (name "+19V") (class "Default")
      (node (ref "19V") (pin "TP") (pinfunction "TP_TP") (pintype "input"))
      (node (ref "D1") (pin "A") (pinfunction "A_A") (pintype "passive"))
      (node (ref "R23") (pin "2") (pinfunction "2_2") (pintype "passive"))
      (node (ref "X2") (pin "14") (pinfunction "KL_14") (pintype "passive"))
      (node (ref "X2") (pin "16") (pinfunction "KL_16") (pintype "passive"))
    )
    (net (code "3") (name "5V") (class "Default")
      (node (ref "C16") (pin "+") (pinfunction "+_+") (pintype "passive"))
      (node (ref "C28") (pin "1") (pinfunction "1_1") (pintype "passive"))
      (node (ref "C29") (pin "1") (pinfunction "1_1") (pintype "passive"))
      (node (ref "C32") (pin "1") (pinfunction "1_1") (pintype "passive"))
      (node (ref "C35") (pin "1") (pinfunction "1_1") (pintype "passive"))
      (node (ref "C38") (pin "1") (pinfunction "1_1") (pintype "passive"))
      (node (ref "D2") (pin "C") (pinfunction "C_C") (pintype "passive"))
      (node (ref "IC2") (pin "5") (pinfunction "IN_5") (pintype "input"))
      (node (ref "IC2") (pin "6") (pinfunction "IN_6") (pintype "input"))
      (node (ref "IC3") (pin "2") (pinfunction "VOUT_2") (pintype "output"))
      (node (ref "U$16") (pin "P$2") (pinfunction "VDD_P$2") (pintype "bidirectional"))
      (node (ref "U$17") (pin "P$2") (pinfunction "VDD_P$2") (pintype "bidirectional"))
      (node (ref "U$18") (pin "P$2") (pinfunction "VDD_P$2") (pintype "bidirectional"))
      (node (ref "U$19") (pin "P$2") (pinfunction "VDD_P$2") (pintype "bidirectional"))
    )
    (net (code "4") (name "AN0") (class "Default")
      (node (ref "AN0") (pin "TP") (pinfunction "TP_TP") (pintype "input"))
      (node (ref "C12") (pin "1") (pinfunction "1_1") (pintype "passive"))
      (node (ref "R18") (pin "1") (pinfunction "1_1") (pintype "passive"))
      (node (ref "R23") (pin "1") (pinfunction "1_1") (pintype "passive"))
      (node (ref "U$14") (pin "76") (pinfunction "PE2/D10[A10/D10]/RXD12/SMISO12/SSCL12/RXDX12/SSLB3/MOSIB/IRQ7-DS/AN0_76") (pintype "bidirectional"))
    )
    (net (code "5") (name "AN1") (class "Default")
      (node (ref "C22") (pin "1") (pinfunction "1_1") (pintype "passive"))
      (node (ref "R35") (pin "2") (pinfunction "2_2") (pintype "passive"))
      (node (ref "U$14") (pin "75") (pinfunction "PE3/D11[A11/D11]/~{CTS12}/~{RTS12}/~{SS12}/MISOB/AN1_75") (pintype "bidirectional"))
    )
    (net (code "6") (name "AN3") (class "Default")
      (node (ref "C40") (pin "1") (pinfunction "1_1") (pintype "passive"))
      (node (ref "R36") (pin "2") (pinfunction "2_2") (pintype "passive"))
      (node (ref "U$14") (pin "73") (pinfunction "PE5/D13[A13/D13]/RSPCKB/IRQ5/AN3_73") (pintype "bidirectional"))
    )
    (net (code "7") (name "AVCC0") (class "Default")
      (node (ref "C13") (pin "1") (pinfunction "1_1") (pintype "passive"))
      (node (ref "L1") (pin "2") (pinfunction "1_2") (pintype "passive"))
      (node (ref "U$14") (pin "96") (pinfunction "VREFH0_96") (pintype "bidirectional"))
      (node (ref "U$14") (pin "97") (pinfunction "AVCC0_97") (pintype "bidirectional"))
    )
    (net (code "8") (name "BAT0_EN") (class "Default")
      (node (ref "U$14") (pin "63") (pinfunction "PA7/A7/MISOA_63") (pintype "bidirectional"))
      (node (ref "X2") (pin "9") (pinfunction "KL_9") (pintype "passive"))
    )
    (net (code "9") (name "BAT1_EN") (class "Default")
      (node (ref "U$14") (pin "59") (pinfunction "PB1/A9/TXD6/SMOSI6/SSDA6/IRQ4-DS_59") (pintype "bidirectional"))
      (node (ref "X2") (pin "11") (pinfunction "KL_11") (pintype "passive"))
    )
    (net (code "10") (name "BAT2_EN") (class "Default")
      (node (ref "U$14") (pin "58") (pinfunction "PB2/A10/~{CTS6}/~{RTS6}/~{SS6}_58") (pintype "bidirectional"))
      (node (ref "X2") (pin "13") (pinfunction "KL_13") (pintype "passive"))
    )
    (net (code "11") (name "BAT3_EN") (class "Default")
      (node (ref "U$14") (pin "57") (pinfunction "PB3/A11/SCK6_57") (pintype "bidirectional"))
      (node (ref "X2") (pin "15") (pinfunction "KL_15") (pintype "passive"))
    )
    (net (code "12") (name "BUZZER") (class "Default")
      (node (ref "R19") (pin "2") (pinfunction "2_2") (pintype "passive"))
      (node (ref "U$14") (pin "100") (pinfunction "P05/IRQ13/DA1_100") (pintype "bidirectional"))
    )
    (net (code "13") (name "COMPUTER_PWR") (class "Default")
      (node (ref "U$14") (pin "78") (pinfunction "PE0/D8[A8/D8]/SCK12/SSLB1/ANEX0_78") (pintype "bidirectional"))
      (node (ref "X2") (pin "28") (pinfunction "KL_28") (pintype "passive"))
    )
    (net (code "14") (name "CPOUT1") (class "Default")
      (node (ref "C20") (pin "1") (pinfunction "1_1") (pintype "passive"))
      (node (ref "U1") (pin "20") (pinfunction "CPOUT_20") (pintype "bidirectional"))
    )
    (net (code "15") (name "CPOUT2") (class "Default")
      (node (ref "C25") (pin "1") (pinfunction "1_1") (pintype "passive"))
      (node (ref "U2") (pin "20") (pinfunction "CPOUT_20") (pintype "bidirectional"))
    )
    (net (code "16") (name "D+") (class "Default")
      (node (ref "CN2") (pin "D+") (pinfunction "D+_D+") (pintype "bidirectional"))
      (node (ref "R25") (pin "2") (pinfunction "2_2") (pintype "passive"))
      (node (ref "U$2") (pin "D+") (pinfunction "D+_D+") (pintype "bidirectional"))
    )
    (net (code "17") (name "D-") (class "Default")
      (node (ref "CN2") (pin "D-") (pinfunction "D-_D-") (pintype "bidirectional"))
      (node (ref "R24") (pin "2") (pinfunction "2_2") (pintype "passive"))
      (node (ref "U$2") (pin "D-") (pinfunction "D-_D-") (pintype "bidirectional"))
    )
    (net (code "18") (name "D0") (class "Default")
      (node (ref "U$14") (pin "86") (pinfunction "PD0/D0[A0/D0]/IRQ0/AN008_86") (pintype "bidirectional"))
      (node (ref "U$3") (pin "P$4") (pinfunction "DB0_P$4") (pintype "bidirectional"))
    )
    (net (code "19") (name "D1") (class "Default")
      (node (ref "U$14") (pin "85") (pinfunction "PD1/D1[A1/D1]/MTIOC4B/IRQ1/AN009_85") (pintype "bidirectional"))
      (node (ref "U$3") (pin "P$5") (pinfunction "DB1_P$5") (pintype "bidirectional"))
    )
    (net (code "20") (name "D2") (class "Default")
      (node (ref "U$14") (pin "84") (pinfunction "PD2/D2[A2/D2]/MTIOC4D/IRQ2/AN010_84") (pintype "bidirectional"))
      (node (ref "U$3") (pin "P$6") (pinfunction "DB2_P$6") (pintype "bidirectional"))
    )
    (net (code "21") (name "D3") (class "Default")
      (node (ref "U$14") (pin "83") (pinfunction "PD3/D3[A3/D3]/~{POE8}/IRQ3/AN011_83") (pintype "bidirectional"))
      (node (ref "U$3") (pin "P$7") (pinfunction "DB3_P$7") (pintype "bidirectional"))
    )
    (net (code "22") (name "D4") (class "Default")
      (node (ref "U$14") (pin "82") (pinfunction "PD4/D4[A4/D4]/~{POE3}/IRQ4/AN012_82") (pintype "bidirectional"))
      (node (ref "U$3") (pin "P$8") (pinfunction "DB4_P$8") (pintype "bidirectional"))
    )
    (net (code "23") (name "D5") (class "Default")
      (node (ref "U$14") (pin "81") (pinfunction "PD5/D5[A5/D5]/MTIC5W/IRQ5/AN013_81") (pintype "bidirectional"))
      (node (ref "U$3") (pin "P$9") (pinfunction "DB5_P$9") (pintype "bidirectional"))
    )
    (net (code "24") (name "D6") (class "Default")
      (node (ref "U$14") (pin "80") (pinfunction "PD6/D6[A6/D6]/MTIC5V/IRQ6/AN6_80") (pintype "bidirectional"))
      (node (ref "U$3") (pin "P$10") (pinfunction "DB6_P$10") (pintype "bidirectional"))
    )
    (net (code "25") (name "D7") (class "Default")
      (node (ref "U$14") (pin "79") (pinfunction "PD7/D7[A7/D7]/MTIC5U/IRQ7/AN7_79") (pintype "bidirectional"))
      (node (ref "U$3") (pin "P$11") (pinfunction "DB7_P$11") (pintype "bidirectional"))
    )
    (net (code "26") (name "EMLE") (class "Default")
      (node (ref "EMLE") (pin "TP") (pinfunction "TP_TP") (pintype "input"))
      (node (ref "JP2") (pin "4") (pinfunction "4_4") (pintype "passive"))
      (node (ref "R15") (pin "1") (pinfunction "1_1") (pintype "passive"))
      (node (ref "U$14") (pin "2") (pinfunction "EMLE_2") (pintype "bidirectional"))
    )
    (net (code "27") (name "ENABLE_PWR") (class "Default")
      (node (ref "U$14") (pin "34") (pinfunction "P12/RXD2/SMISO2/SSCL2/SCL0[FM+]/IRQ2_34") (pintype "bidirectional"))
      (node (ref "X2") (pin "30") (pinfunction "KL_30") (pintype "passive"))
    )
    (net (code "28") (name "EXTAL") (class "Default")
      (node (ref "C7") (pin "2") (pinfunction "2_2") (pintype "passive"))
      (node (ref "U$14") (pin "13") (pinfunction "EXTAL/P36_13") (pintype "bidirectional"))
      (node (ref "X1") (pin "P$2") (pinfunction "P$2_P$2") (pintype "bidirectional"))
    )
    (net (code "29") (name "GND") (class "Default")
      (node (ref "C1") (pin "2") (pinfunction "2_2") (pintype "passive"))
      (node (ref "C10") (pin "2") (pinfunction "2_2") (pintype "passive"))
      (node (ref "C11") (pin "1") (pinfunction "1_1") (pintype "passive"))
      (node (ref "C12") (pin "2") (pinfunction "2_2") (pintype "passive"))
      (node (ref "C13") (pin "2") (pinfunction "2_2") (pintype "passive"))
      (node (ref "C14") (pin "2") (pinfunction "2_2") (pintype "passive"))
      (node (ref "C15") (pin "2") (pinfunction "2_2") (pintype "passive"))
      (node (ref "C16") (pin "-") (pinfunction "-_-") (pintype "passive"))
      (node (ref "C17") (pin "2") (pinfunction "2_2") (pintype "passive"))
      (node (ref "C18") (pin "-") (pinfunction "-_-") (pintype "passive"))
      (node (ref "C19") (pin "2") (pinfunction "2_2") (pintype "passive"))
      (node (ref "C2") (pin "2") (pinfunction "2_2") (pintype "passive"))
      (node (ref "C20") (pin "2") (pinfunction "2_2") (pintype "passive"))
      (node (ref "C21") (pin "2") (pinfunction "2_2") (pintype "passive"))
      (node (ref "C22") (pin "2") (pinfunction "2_2") (pintype "passive"))
      (node (ref "C23") (pin "2") (pinfunction "2_2") (pintype "passive"))
      (node (ref "C24") (pin "2") (pinfunction "2_2") (pintype "passive"))
      (node (ref "C25") (pin "2") (pinfunction "2_2") (pintype "passive"))
      (node (ref "C26") (pin "2") (pinfunction "2_2") (pintype "passive"))
      (node (ref "C28") (pin "2") (pinfunction "2_2") (pintype "passive"))
      (node (ref "C29") (pin "2") (pinfunction "2_2") (pintype "passive"))
      (node (ref "C3") (pin "2") (pinfunction "2_2") (pintype "passive"))
      (node (ref "C30") (pin "2") (pinfunction "2_2") (pintype "passive"))
      (node (ref "C32") (pin "2") (pinfunction "2_2") (pintype "passive"))
      (node (ref "C33") (pin "2") (pinfunction "2_2") (pintype "passive"))
      (node (ref "C35") (pin "2") (pinfunction "2_2") (pintype "passive"))
      (node (ref "C36") (pin "2") (pinfunction "2_2") (pintype "passive"))
      (node (ref "C38") (pin "2") (pinfunction "2_2") (pintype "passive"))
      (node (ref "C39") (pin "2") (pinfunction "2_2") (pintype "passive"))
      (node (ref "C4") (pin "1") (pinfunction "1_1") (pintype "passive"))
      (node (ref "C40") (pin "2") (pinfunction "2_2") (pintype "passive"))
      (node (ref "C41") (pin "-") (pinfunction "-_-") (pintype "passive"))
      (node (ref "C42") (pin "-") (pinfunction "-_-") (pintype "passive"))
      (node (ref "C43") (pin "-") (pinfunction "-_-") (pintype "passive"))
      (node (ref "C44") (pin "-") (pinfunction "-_-") (pintype "passive"))
      (node (ref "C45") (pin "-") (pinfunction "-_-") (pintype "passive"))
      (node (ref "C46") (pin "2") (pinfunction "2_2") (pintype "passive"))
      (node (ref "C47") (pin "2") (pinfunction "2_2") (pintype "passive"))
      (node (ref "C48") (pin "2") (pinfunction "2_2") (pintype "passive"))
      (node (ref "C49") (pin "2") (pinfunction "2_2") (pintype "passive"))
      (node (ref "C5") (pin "2") (pinfunction "2_2") (pintype "passive"))
      (node (ref "C6") (pin "1") (pinfunction "1_1") (pintype "passive"))
      (node (ref "C7") (pin "1") (pinfunction "1_1") (pintype "passive"))
      (node (ref "C8") (pin "2") (pinfunction "2_2") (pintype "passive"))
      (node (ref "C9") (pin "1") (pinfunction "1_1") (pintype "passive"))
      (node (ref "CN2") (pin "GND") (pinfunction "GND_GND") (pintype "power_in"))
      (node (ref "D8") (pin "2") (pinfunction "CATHODE_2") (pintype "bidirectional"))
      (node (ref "IC2") (pin "3") (pinfunction "~{EN}_3") (pintype "input"))
      (node (ref "IC2") (pin "4") (pinfunction "GND_4") (pintype "power_in"))
      (node (ref "IC3") (pin "1") (pinfunction "GND_1") (pintype "power_in"))
      (node (ref "JP2") (pin "12") (pinfunction "12_12") (pintype "passive"))
      (node (ref "JP2") (pin "14") (pinfunction "14_14") (pintype "passive"))
      (node (ref "JP2") (pin "2") (pinfunction "2_2") (pintype "passive"))
      (node (ref "R12") (pin "1") (pinfunction "1_1") (pintype "passive"))
      (node (ref "R13") (pin "2") (pinfunction "2_2") (pintype "passive"))
      (node (ref "R14") (pin "1") (pinfunction "1_1") (pintype "passive"))
      (node (ref "R15") (pin "2") (pinfunction "2_2") (pintype "passive"))
      (node (ref "R17") (pin "2") (pinfunction "2_2") (pintype "passive"))
      (node (ref "R18") (pin "2") (pinfunction "2_2") (pintype "passive"))
      (node (ref "R2") (pin "2") (pinfunction "2_2") (pintype "passive"))
      (node (ref "R26") (pin "2") (pinfunction "2_2") (pintype "passive"))
      (node (ref "R28") (pin "1") (pinfunction "1_1") (pintype "passive"))
      (node (ref "R29") (pin "1") (pinfunction "1_1") (pintype "passive"))
      (node (ref "R30") (pin "1") (pinfunction "1_1") (pintype "passive"))
      (node (ref "R31") (pin "1") (pinfunction "1_1") (pintype "passive"))
      (node (ref "R4") (pin "2") (pinfunction "2_2") (pintype "passive"))
      (node (ref "R7") (pin "1") (pinfunction "1_1") (pintype "passive"))
      (node (ref "R8") (pin "1") (pinfunction "1_1") (pintype "passive"))
      (node (ref "S1") (pin "2") (pinfunction "2_2") (pintype "passive"))
      (node (ref "S2") (pin "1") (pinfunction "1_1") (pintype "passive"))
      (node (ref "S2") (pin "2") (pinfunction "2_2") (pintype "passive"))
      (node (ref "S6") (pin "1") (pinfunction "1_1") (pintype "passive"))
      (node (ref "S6") (pin "2") (pinfunction "2_2") (pintype "passive"))
      (node (ref "S7") (pin "1") (pinfunction "1_1") (pintype "passive"))
      (node (ref "S7") (pin "2") (pinfunction "2_2") (pintype "passive"))
      (node (ref "S8") (pin "1") (pinfunction "1_1") (pintype "passive"))
      (node (ref "S8") (pin "2") (pinfunction "2_2") (pintype "passive"))
      (node (ref "S9") (pin "2") (pinfunction "2_2") (pintype "passive"))
      (node (ref "SG1") (pin "2") (pinfunction "2_2") (pintype "passive"))
      (node (ref "U$1") (pin "N") (pinfunction "N_N") (pintype "bidirectional"))
      (node (ref "U$14") (pin "12") (pinfunction "VSS_12") (pintype "bidirectional"))
      (node (ref "U$14") (pin "3") (pinfunction "VREFL_3") (pintype "bidirectional"))
      (node (ref "U$14") (pin "38") (pinfunction "VSS_USB_38") (pintype "bidirectional"))
      (node (ref "U$14") (pin "62") (pinfunction "VSS_62") (pintype "bidirectional"))
      (node (ref "U$14") (pin "94") (pinfunction "VREFL0_94") (pintype "bidirectional"))
      (node (ref "U$14") (pin "99") (pinfunction "AVSS0_99") (pintype "bidirectional"))
      (node (ref "U$16") (pin "P$3") (pinfunction "GND_P$3") (pintype "bidirectional"))
      (node (ref "U$16") (pin "PAD@1") (pinfunction "PAD_PAD@1") (pintype "bidirectional"))
      (node (ref "U$17") (pin "P$3") (pinfunction "GND_P$3") (pintype "bidirectional"))
      (node (ref "U$17") (pin "PAD@1") (pinfunction "PAD_PAD@1") (pintype "bidirectional"))
      (node (ref "U$18") (pin "P$3") (pinfunction "GND_P$3") (pintype "bidirectional"))
      (node (ref "U$18") (pin "PAD@1") (pinfunction "PAD_PAD@1") (pintype "bidirectional"))
      (node (ref "U$19") (pin "P$3") (pinfunction "GND_P$3") (pintype "bidirectional"))
      (node (ref "U$19") (pin "PAD@1") (pinfunction "PAD_PAD@1") (pintype "bidirectional"))
      (node (ref "U$2") (pin "GND") (pinfunction "GND_GND") (pintype "bidirectional"))
      (node (ref "U$2") (pin "S1") (pinfunction "P$1_S1") (pintype "bidirectional"))
      (node (ref "U$2") (pin "S2") (pinfunction "P$2_S2") (pintype "bidirectional"))
      (node (ref "U$3") (pin "P$1") (pinfunction "VSS_P$1") (pintype "bidirectional"))
      (node (ref "U1") (pin "1") (pinfunction "CLKIN_1") (pintype "bidirectional"))
      (node (ref "U1") (pin "18") (pinfunction "GND_18") (pintype "bidirectional"))
      (node (ref "U2") (pin "1") (pinfunction "CLKIN_1") (pintype "bidirectional"))
      (node (ref "U2") (pin "18") (pinfunction "GND_18") (pintype "bidirectional"))
      (node (ref "X2") (pin "10") (pinfunction "KL_10") (pintype "passive"))
      (node (ref "X2") (pin "17") (pinfunction "KL_17") (pintype "passive"))
      (node (ref "X3") (pin "2") (pinfunction "S_2") (pintype "passive"))
    )
    (net (code "30") (name "IBAT0_AD") (class "Default")
      (node (ref "C17") (pin "1") (pinfunction "1_1") (pintype "passive"))
      (node (ref "U$14") (pin "90") (pinfunction "P44/IRQ12-DS/AN004_90") (pintype "bidirectional"))
      (node (ref "X2") (pin "19") (pinfunction "KL_19") (pintype "passive"))
    )
    (net (code "31") (name "IBAT1_AD") (class "Default")
      (node (ref "C10") (pin "1") (pinfunction "1_1") (pintype "passive"))
      (node (ref "U$14") (pin "89") (pinfunction "P45/IRQ13-DS/AN005_89") (pintype "bidirectional"))
      (node (ref "X2") (pin "21") (pinfunction "KL_21") (pintype "passive"))
    )
    (net (code "32") (name "IBAT2_AD") (class "Default")
      (node (ref "C3") (pin "1") (pinfunction "1_1") (pintype "passive"))
      (node (ref "U$14") (pin "88") (pinfunction "P46/IRQ14-DS/AN006_88") (pintype "bidirectional"))
      (node (ref "X2") (pin "23") (pinfunction "KL_23") (pintype "passive"))
    )
    (net (code "33") (name "IBAT3_AD") (class "Default")
      (node (ref "C5") (pin "1") (pinfunction "1_1") (pintype "passive"))
      (node (ref "U$14") (pin "87") (pinfunction "P47/IRQ15-DS/AN007_87") (pintype "bidirectional"))
      (node (ref "X2") (pin "25") (pinfunction "KL_25") (pintype "passive"))
    )
    (net (code "34") (name "IMON1") (class "Default")
      (node (ref "R35") (pin "1") (pinfunction "1_1") (pintype "passive"))
      (node (ref "X2") (pin "27") (pinfunction "KL_27") (pintype "passive"))
    )
    (net (code "35") (name "IMON2") (class "Default")
      (node (ref "R36") (pin "1") (pinfunction "1_1") (pintype "passive"))
      (node (ref "X2") (pin "29") (pinfunction "KL_29") (pintype "passive"))
    )
    (net (code "36") (name "INT_GYRO1") (class "Default")
      (node (ref "U$14") (pin "51") (pinfunction "PC1/A17/SCK5/SSLA2/IRQ12_51") (pintype "bidirectional"))
      (node (ref "U1") (pin "12") (pinfunction "INT_12") (pintype "bidirectional"))
    )
    (net (code "37") (name "INT_GYRO2") (class "Default")
      (node (ref "U$14") (pin "52") (pinfunction "PC0/A16/~{CTS5}/~{RTS5}/~{SS5}/SSLA1/IRQ14_52") (pintype "bidirectional"))
      (node (ref "U2") (pin "12") (pinfunction "INT_12") (pintype "bidirectional"))
    )
    (net (code "38") (name "LED0") (class "Default")
      (node (ref "LED0") (pin "A") (pinfunction "A_A") (pintype "passive"))
      (node (ref "TPLED0") (pin "TP") (pinfunction "TP_TP") (pintype "input"))
      (node (ref "U$14") (pin "28") (pinfunction "P20/TXD0/SMOSI0/SSDA0/IRQ8_28") (pintype "bidirectional"))
    )
    (net (code "39") (name "LED1") (class "Default")
      (node (ref "LED1") (pin "A") (pinfunction "A_A") (pintype "passive"))
      (node (ref "TPLED1") (pin "TP") (pinfunction "TP_TP") (pintype "input"))
      (node (ref "U$14") (pin "27") (pinfunction "P21/RXD0/SMISO0/SSCL0/IRQ9_27") (pintype "bidirectional"))
    )
    (net (code "40") (name "LED2") (class "Default")
      (node (ref "LED2") (pin "A") (pinfunction "A_A") (pintype "passive"))
      (node (ref "TPLED2") (pin "TP") (pinfunction "TP_TP") (pintype "input"))
      (node (ref "U$14") (pin "26") (pinfunction "P22/SCK0_26") (pintype "bidirectional"))
    )
    (net (code "41") (name "LED3") (class "Default")
      (node (ref "LED3") (pin "A") (pinfunction "A_A") (pintype "passive"))
      (node (ref "TPLED3") (pin "TP") (pinfunction "TP_TP") (pintype "input"))
      (node (ref "U$14") (pin "25") (pinfunction "P23/TXD3/~{CTS0}/~{RTS0}/SMOSI3/~{SS0}/SSDA3_25") (pintype "bidirectional"))
    )
    (net (code "42") (name "LED4") (class "Default")
      (node (ref "LED4") (pin "A") (pinfunction "A_A") (pintype "passive"))
      (node (ref "TPLED4") (pin "TP") (pinfunction "TP_TP") (pintype "input"))
      (node (ref "U$14") (pin "24") (pinfunction "P24/~{CS4}/SCK3_24") (pintype "bidirectional"))
    )
    (net (code "43") (name "LED5") (class "Default")
      (node (ref "LED5") (pin "A") (pinfunction "A_A") (pintype "passive"))
      (node (ref "TPLED5") (pin "TP") (pinfunction "TP_TP") (pintype "input"))
      (node (ref "U$14") (pin "23") (pinfunction "P25/~{CS5}/RXD3/SMISO3/SSCL3/~{ADTRG0}_23") (pintype "bidirectional"))
    )
    (net (code "44") (name "LED6{slash}TDO") (class "Default")
      (node (ref "JP2") (pin "5") (pinfunction "5_5") (pintype "passive"))
      (node (ref "LED6") (pin "A") (pinfunction "A_A") (pintype "passive"))
      (node (ref "TPLED6") (pin "TP") (pinfunction "TP_TP") (pintype "input"))
      (node (ref "U$14") (pin "22") (pinfunction "TDO/P26/~{CS6}/TXD1/~{CTS3}/~{RTS3}/SMOSI1/~{SS3}/SSDA1/MOSIB_22") (pintype "bidirectional"))
    )
    (net (code "45") (name "LED7{slash}TCK") (class "Default")
      (node (ref "JP2") (pin "1") (pinfunction "1_1") (pintype "passive"))
      (node (ref "JP2") (pin "11") (pinfunction "11_11") (pintype "passive"))
      (node (ref "LED7") (pin "A") (pinfunction "A_A") (pintype "passive"))
      (node (ref "TPLED7") (pin "TP") (pinfunction "TP_TP") (pintype "input"))
      (node (ref "U$14") (pin "21") (pinfunction "TCK/FINEC/P27/~{CS7}/MTIOC2B/TMCI3/PO7/SCK1/RSPCKB_21") (pintype "bidirectional"))
    )
    (net (code "46") (name "LED_BLUE") (class "Default")
      (node (ref "R34") (pin "2") (pinfunction "2_2") (pintype "passive"))
      (node (ref "U$14") (pin "33") (pinfunction "P13/TXD2/SMOSI2/SSDA2/SDA0[FM+]/IRQ3/~{ADTRG}_33") (pintype "bidirectional"))
    )
    (net (code "47") (name "LED_GREEN") (class "Default")
      (node (ref "R33") (pin "2") (pinfunction "2_2") (pintype "passive"))
      (node (ref "U$14") (pin "31") (pinfunction "P15/RXD1/SCK3/SMISO1/SSCL1/CRX1-DS/IRQ5_31") (pintype "bidirectional"))
    )
    (net (code "48") (name "LED_RED") (class "Default")
      (node (ref "R32") (pin "2") (pinfunction "2_2") (pintype "passive"))
      (node (ref "U$14") (pin "29") (pinfunction "P17/SCK1/TXD3/SMOSI3/SSDA3/MISOA/SDA2-DS/IETXD/IRQ7/~{ADTRG}_29") (pintype "bidirectional"))
    )
    (net (code "49") (name "MD") (class "Default")
      (node (ref "JP2") (pin "7") (pinfunction "7_7") (pintype "passive"))
      (node (ref "R5") (pin "1") (pinfunction "1_1") (pintype "passive"))
      (node (ref "S1") (pin "1") (pinfunction "1_1") (pintype "passive"))
      (node (ref "U$14") (pin "7") (pinfunction "MD/FINED_7") (pintype "bidirectional"))
    )
    (net (code "50") (name "MISOA") (class "Default")
      (node (ref "R9") (pin "2") (pinfunction "2_2") (pintype "passive"))
      (node (ref "U$14") (pin "45") (pinfunction "PC7/A23/~{CS0}/TXD8/SMOSI8/SSDA8/MISOA/IRQ14_45") (pintype "bidirectional"))
      (node (ref "U2") (pin "9") (pinfunction "AD0/SDO_9") (pintype "bidirectional"))
    )
    (net (code "51") (name "MISOB") (class "Default")
      (node (ref "U$14") (pin "71") (pinfunction "PE7/D15[A15/D15]/MISOB/IRQ7/AN5_71") (pintype "bidirectional"))
      (node (ref "U1") (pin "9") (pinfunction "AD0/SDO_9") (pintype "bidirectional"))
    )
    (net (code "52") (name "MOSIA") (class "Default")
      (node (ref "U$14") (pin "46") (pinfunction "PC6/A22/~{CS1}/RXD8/SMISO8/SSCL8/MOSIA/IRQ13_46") (pintype "bidirectional"))
      (node (ref "U2") (pin "24") (pinfunction "SDA/SDI_24") (pintype "bidirectional"))
    )
    (net (code "53") (name "MOSIB") (class "Default")
      (node (ref "U$14") (pin "72") (pinfunction "PE6/D14[A14/D14]/MOSIB/IRQ6/AN4_72") (pintype "bidirectional"))
      (node (ref "U1") (pin "24") (pinfunction "SDA/SDI_24") (pintype "bidirectional"))
    )
    (net (code "54") (name "NMI") (class "Default")
      (node (ref "R6") (pin "1") (pinfunction "1_1") (pintype "passive"))
      (node (ref "U$14") (pin "15") (pinfunction "P35/NMI_15") (pintype "bidirectional"))
    )
    (net (code "55") (name "Net-(D8-BLUE_CATHODE)") (class "Default")
      (node (ref "D8") (pin "4") (pinfunction "BLUE_CATHODE_4") (pintype "bidirectional"))
      (node (ref "R34") (pin "1") (pinfunction "1_1") (pintype "passive"))
    )
    (net (code "56") (name "Net-(D8-GREEN_CATHODE)") (class "Default")
      (node (ref "D8") (pin "3") (pinfunction "GREEN_CATHODE_3") (pintype "bidirectional"))
      (node (ref "R33") (pin "1") (pinfunction "1_1") (pintype "passive"))
    )
    (net (code "57") (name "Net-(D8-RED_CATHODE)") (class "Default")
      (node (ref "D8") (pin "1") (pinfunction "RED_CATHODE_1") (pintype "bidirectional"))
      (node (ref "R32") (pin "1") (pinfunction "1_1") (pintype "passive"))
    )
    (net (code "58") (name "Net-(LED0-PadC)") (class "Default")
      (node (ref "LED0") (pin "C") (pinfunction "C_C") (pintype "passive"))
      (node (ref "R7") (pin "2") (pinfunction "2_2") (pintype "passive"))
    )
    (net (code "59") (name "Net-(LED1-PadC)") (class "Default")
      (node (ref "LED1") (pin "C") (pinfunction "C_C") (pintype "passive"))
      (node (ref "R8") (pin "2") (pinfunction "2_2") (pintype "passive"))
    )
    (net (code "60") (name "Net-(LED2-PadC)") (class "Default")
      (node (ref "LED2") (pin "C") (pinfunction "C_C") (pintype "passive"))
      (node (ref "R12") (pin "2") (pinfunction "2_2") (pintype "passive"))
    )
    (net (code "61") (name "Net-(LED3-PadC)") (class "Default")
      (node (ref "LED3") (pin "C") (pinfunction "C_C") (pintype "passive"))
      (node (ref "R14") (pin "2") (pinfunction "2_2") (pintype "passive"))
    )
    (net (code "62") (name "Net-(LED4-PadC)") (class "Default")
      (node (ref "LED4") (pin "C") (pinfunction "C_C") (pintype "passive"))
      (node (ref "R28") (pin "2") (pinfunction "2_2") (pintype "passive"))
    )
    (net (code "63") (name "Net-(LED5-PadC)") (class "Default")
      (node (ref "LED5") (pin "C") (pinfunction "C_C") (pintype "passive"))
      (node (ref "R29") (pin "2") (pinfunction "2_2") (pintype "passive"))
    )
    (net (code "64") (name "Net-(LED6-PadC)") (class "Default")
      (node (ref "LED6") (pin "C") (pinfunction "C_C") (pintype "passive"))
      (node (ref "R30") (pin "2") (pinfunction "2_2") (pintype "passive"))
    )
    (net (code "65") (name "Net-(LED7-PadC)") (class "Default")
      (node (ref "LED7") (pin "C") (pinfunction "C_C") (pintype "passive"))
      (node (ref "R31") (pin "2") (pinfunction "2_2") (pintype "passive"))
    )
    (net (code "66") (name "Net-(R19-Pad1)") (class "Default")
      (node (ref "R19") (pin "1") (pinfunction "1_1") (pintype "passive"))
      (node (ref "SG1") (pin "1") (pinfunction "1_1") (pintype "passive"))
    )
    (net (code "67") (name "Net-(U$14-P14{slash}~{CTS1}{slash}~{RTS1}{slash}~{SS1}{slash}CTX1{slash}USB0_DPUPE{slash}IRQ4)") (class "Default")
      (node (ref "R10") (pin "1") (pinfunction "1_1") (pintype "passive"))
      (node (ref "U$14") (pin "32") (pinfunction "P14/~{CTS1}/~{RTS1}/~{SS1}/CTX1/USB0_DPUPE/IRQ4_32") (pintype "bidirectional"))
    )
    (net (code "68") (name "Net-(U$14-VCL)") (class "Default")
      (node (ref "C4") (pin "2") (pinfunction "2_2") (pintype "passive"))
      (node (ref "U$14") (pin "5") (pinfunction "VCL_5") (pintype "bidirectional"))
    )
    (net (code "69") (name "Net-(U$16-BOOT)") (class "Default")
      (node (ref "C27") (pin "1") (pinfunction "1_1") (pintype "passive"))
      (node (ref "U$16") (pin "P$7") (pinfunction "BOOT_P$7") (pintype "bidirectional"))
    )
    (net (code "70") (name "Net-(U$16-BOOT_R)") (class "Default")
      (node (ref "C27") (pin "2") (pinfunction "2_2") (pintype "passive"))
      (node (ref "U$16") (pin "P$6") (pinfunction "BOOT_R_P$6") (pintype "bidirectional"))
    )
    (net (code "71") (name "Net-(U$17-BOOT)") (class "Default")
      (node (ref "C31") (pin "1") (pinfunction "1_1") (pintype "passive"))
      (node (ref "U$17") (pin "P$7") (pinfunction "BOOT_P$7") (pintype "bidirectional"))
    )
    (net (code "72") (name "Net-(U$17-BOOT_R)") (class "Default")
      (node (ref "C31") (pin "2") (pinfunction "2_2") (pintype "passive"))
      (node (ref "U$17") (pin "P$6") (pinfunction "BOOT_R_P$6") (pintype "bidirectional"))
    )
    (net (code "73") (name "Net-(U$18-BOOT)") (class "Default")
      (node (ref "C34") (pin "1") (pinfunction "1_1") (pintype "passive"))
      (node (ref "U$18") (pin "P$7") (pinfunction "BOOT_P$7") (pintype "bidirectional"))
    )
    (net (code "74") (name "Net-(U$18-BOOT_R)") (class "Default")
      (node (ref "C34") (pin "2") (pinfunction "2_2") (pintype "passive"))
      (node (ref "U$18") (pin "P$6") (pinfunction "BOOT_R_P$6") (pintype "bidirectional"))
    )
    (net (code "75") (name "Net-(U$19-BOOT)") (class "Default")
      (node (ref "C37") (pin "1") (pinfunction "1_1") (pintype "passive"))
      (node (ref "U$19") (pin "P$7") (pinfunction "BOOT_P$7") (pintype "bidirectional"))
    )
    (net (code "76") (name "Net-(U$19-BOOT_R)") (class "Default")
      (node (ref "C37") (pin "2") (pinfunction "2_2") (pintype "passive"))
      (node (ref "U$19") (pin "P$6") (pinfunction "BOOT_R_P$6") (pintype "bidirectional"))
    )
    (net (code "77") (name "OUT1_EN") (class "Default")
      (node (ref "U$14") (pin "55") (pinfunction "PB5/A13/SCK9_55") (pintype "bidirectional"))
      (node (ref "X2") (pin "18") (pinfunction "KL_18") (pintype "passive"))
    )
    (net (code "78") (name "OUT2_EN") (class "Default")
      (node (ref "U$14") (pin "53") (pinfunction "PB7/A15/TXD9/SMOSI9/SSDA9_53") (pintype "bidirectional"))
      (node (ref "X2") (pin "20") (pinfunction "KL_20") (pintype "passive"))
    )
    (net (code "79") (name "OUT3_EN") (class "Default")
      (node (ref "U$14") (pin "4") (pinfunction "PJ3/MTIOC3C/~{CTS6}/~{RTS6}/~{CTS0}/~{RTS0}/~{SS6}/~{SS0}_4") (pintype "bidirectional"))
      (node (ref "X2") (pin "22") (pinfunction "KL_22") (pintype "passive"))
    )
    (net (code "80") (name "OUT4_EN") (class "Default")
      (node (ref "U$14") (pin "41") (pinfunction "BCLK/P53_41") (pintype "bidirectional"))
      (node (ref "X2") (pin "24") (pinfunction "KL_24") (pintype "passive"))
    )
    (net (code "81") (name "OUT5_EN") (class "Default")
      (node (ref "U$14") (pin "98") (pinfunction "P07/IRQ15/~{ADTRG0}_98") (pintype "bidirectional"))
      (node (ref "X2") (pin "26") (pinfunction "KL_26") (pintype "passive"))
    )
    (net (code "82") (name "PGOOD1") (class "Default")
      (node (ref "U$14") (pin "49") (pinfunction "A19/TXD5/SMOSI5/SSDA5/IETXD_49") (pintype "bidirectional"))
      (node (ref "X2") (pin "31") (pinfunction "KL_31") (pintype "passive"))
    )
    (net (code "83") (name "PGOOD2") (class "Default")
      (node (ref "U$14") (pin "50") (pinfunction "PC2/A18/RXD5/SMISO5/SSCL5/SSLA3/IERXD_50") (pintype "bidirectional"))
      (node (ref "X2") (pin "33") (pinfunction "KL_33") (pintype "passive"))
    )
    (net (code "84") (name "PWM0") (class "Default")
      (node (ref "U$14") (pin "70") (pinfunction "PA0/A0/~{BC0}/SSLA1_70") (pintype "bidirectional"))
      (node (ref "U$16") (pin "P$8") (pinfunction "PWM_P$8") (pintype "bidirectional"))
    )
    (net (code "85") (name "PWM1") (class "Default")
      (node (ref "U$14") (pin "66") (pinfunction "PA4/A4/TXD5/SMOSI5/SSDA5/SSLA0/IRQ5-DS_66") (pintype "bidirectional"))
      (node (ref "U$17") (pin "P$8") (pinfunction "PWM_P$8") (pintype "bidirectional"))
    )
    (net (code "86") (name "PWM2") (class "Default")
      (node (ref "U$14") (pin "64") (pinfunction "PA6/A6/~{CTS5}/~{RTS5}/~{SS5}/MOSIA_64") (pintype "bidirectional"))
      (node (ref "U$18") (pin "P$8") (pinfunction "PWM_P$8") (pintype "bidirectional"))
    )
    (net (code "87") (name "PWM3") (class "Default")
      (node (ref "U$14") (pin "61") (pinfunction "PB0/A8/RXD6/SMISO6/SSCL6/RSPCKA/IRQ12_61") (pintype "bidirectional"))
      (node (ref "U$19") (pin "P$8") (pinfunction "PWM_P$8") (pintype "bidirectional"))
    )
    (net (code "88") (name "PWM4") (class "Default")
      (node (ref "U$14") (pin "56") (pinfunction "PB4/A12/~{CTS9}/~{RTS9}/~{SS9}_56") (pintype "bidirectional"))
      (node (ref "X2") (pin "34") (pinfunction "KL_34") (pintype "passive"))
    )
    (net (code "89") (name "PWM5") (class "Default")
      (node (ref "U$14") (pin "54") (pinfunction "PB6/A14/RXD9/SMISO9/SSCL9_54") (pintype "bidirectional"))
      (node (ref "X2") (pin "32") (pinfunction "KL_32") (pintype "passive"))
    )
    (net (code "90") (name "REGOUT1") (class "Default")
      (node (ref "C19") (pin "1") (pinfunction "1_1") (pintype "passive"))
      (node (ref "U1") (pin "10") (pinfunction "REGOUT_10") (pintype "bidirectional"))
    )
    (net (code "91") (name "REGOUT2") (class "Default")
      (node (ref "C24") (pin "1") (pinfunction "1_1") (pintype "passive"))
      (node (ref "U2") (pin "10") (pinfunction "REGOUT_10") (pintype "bidirectional"))
    )
    (net (code "92") (name "RSPCKA") (class "Default")
      (node (ref "U$14") (pin "47") (pinfunction "PC5/A21/~{CS2}/~{WAIT}/SCK8/RSPCKA_47") (pintype "bidirectional"))
      (node (ref "U2") (pin "23") (pinfunction "SCL/SCLK_23") (pintype "bidirectional"))
    )
    (net (code "93") (name "RSPCKB") (class "Default")
      (node (ref "U$14") (pin "77") (pinfunction "PE1/D9[A9/D9]/TXD12/SMOSI12/SSDA12/TXDX12/SIOX12/SSLB2/RSPCKB/ANEX1_77") (pintype "bidirectional"))
      (node (ref "U1") (pin "23") (pinfunction "SCL/SCLK_23") (pintype "bidirectional"))
    )
    (net (code "94") (name "SSLA0") (class "Default")
      (node (ref "U$14") (pin "48") (pinfunction "PC4/A20/~{CS3}/SCK5/~{CTS8}/~{RTS8}/~{SS8}/SSLA0_48") (pintype "bidirectional"))
      (node (ref "U2") (pin "8") (pinfunction "CS_8") (pintype "bidirectional"))
    )
    (net (code "95") (name "SSLB0") (class "Default")
      (node (ref "U$14") (pin "74") (pinfunction "PE4/D12[A12/D12]/SSLB0/AN2_74") (pintype "bidirectional"))
      (node (ref "U1") (pin "8") (pinfunction "CS_8") (pintype "bidirectional"))
    )
    (net (code "96") (name "SUPERCAP") (class "Default")
      (node (ref "D7") (pin "3") (pinfunction "C_3") (pintype "passive"))
      (node (ref "U$1") (pin "P") (pinfunction "P_P") (pintype "bidirectional"))
      (node (ref "U$14") (pin "6") (pinfunction "VBATT_6") (pintype "bidirectional"))
    )
    (net (code "97") (name "USB0_DM") (class "Default")
      (node (ref "R24") (pin "1") (pinfunction "1_1") (pintype "passive"))
      (node (ref "U$14") (pin "36") (pinfunction "USB0_DM_36") (pintype "bidirectional"))
    )
    (net (code "98") (name "USB0_DP") (class "Default")
      (node (ref "R10") (pin "2") (pinfunction "2_2") (pintype "passive"))
      (node (ref "R25") (pin "1") (pinfunction "1_1") (pintype "passive"))
      (node (ref "U$14") (pin "37") (pinfunction "USB0_DP_37") (pintype "bidirectional"))
    )
    (net (code "99") (name "USB0_VBUS") (class "Default")
      (node (ref "R26") (pin "1") (pinfunction "1_1") (pintype "passive"))
      (node (ref "R27") (pin "2") (pinfunction "2_2") (pintype "passive"))
      (node (ref "U$14") (pin "30") (pinfunction "P16/TXD1/RXD3/SMOSI1/SMISO3/SSDA1/SSCL3/MOSIA/SCL2-DS/IERXD/USB0_VBUS/IRQ6/~{ADTRG0}_30") (pintype "bidirectional"))
    )
    (net (code "100") (name "V+") (class "Default")
      (node (ref "C23") (pin "1") (pinfunction "1_1") (pintype "passive"))
      (node (ref "C41") (pin "+") (pinfunction "+_+") (pintype "passive"))
      (node (ref "IC3") (pin "3") (pinfunction "VIN_3") (pintype "input"))
      (node (ref "X2") (pin "12") (pinfunction "KL_12") (pintype "passive"))
    )
    (net (code "101") (name "VBAT0") (class "Default")
      (node (ref "C42") (pin "+") (pinfunction "+_+") (pintype "passive"))
      (node (ref "L2") (pin "2") (pinfunction "2_2") (pintype "passive"))
      (node (ref "R16") (pin "1") (pinfunction "1_1") (pintype "passive"))
      (node (ref "VBAT0") (pin "TP") (pinfunction "TP_TP") (pintype "input"))
      (node (ref "X2") (pin "1") (pinfunction "KL_1") (pintype "passive"))
      (node (ref "X2") (pin "2") (pinfunction "KL_2") (pintype "passive"))
    )
    (net (code "102") (name "VBAT0_AD") (class "Default")
      (node (ref "C15") (pin "1") (pinfunction "1_1") (pintype "passive"))
      (node (ref "R16") (pin "2") (pinfunction "2_2") (pintype "passive"))
      (node (ref "R17") (pin "1") (pinfunction "1_1") (pintype "passive"))
      (node (ref "U$14") (pin "95") (pinfunction "P40/IRQ8-DS/AN000_95") (pintype "bidirectional"))
    )
    (net (code "103") (name "VBAT1") (class "Default")
      (node (ref "C43") (pin "+") (pinfunction "+_+") (pintype "passive"))
      (node (ref "L3") (pin "2") (pinfunction "2_2") (pintype "passive"))
      (node (ref "R11") (pin "1") (pinfunction "1_1") (pintype "passive"))
      (node (ref "VBAT1") (pin "TP") (pinfunction "TP_TP") (pintype "input"))
      (node (ref "X2") (pin "3") (pinfunction "KL_3") (pintype "passive"))
      (node (ref "X2") (pin "4") (pinfunction "KL_4") (pintype "passive"))
    )
    (net (code "104") (name "VBAT1_AD") (class "Default")
      (node (ref "C8") (pin "1") (pinfunction "1_1") (pintype "passive"))
      (node (ref "R11") (pin "2") (pinfunction "2_2") (pintype "passive"))
      (node (ref "R13") (pin "1") (pinfunction "1_1") (pintype "passive"))
      (node (ref "U$14") (pin "93") (pinfunction "P41/IRQ9-DS/AN001_93") (pintype "bidirectional"))
    )
    (net (code "105") (name "VBAT2") (class "Default")
      (node (ref "C44") (pin "+") (pinfunction "+_+") (pintype "passive"))
      (node (ref "L4") (pin "2") (pinfunction "2_2") (pintype "passive"))
      (node (ref "R3") (pin "1") (pinfunction "1_1") (pintype "passive"))
      (node (ref "VBAT2") (pin "TP") (pinfunction "TP_TP") (pintype "input"))
      (node (ref "X2") (pin "5") (pinfunction "KL_5") (pintype "passive"))
      (node (ref "X2") (pin "6") (pinfunction "KL_6") (pintype "passive"))
    )
    (net (code "106") (name "VBAT2_AD") (class "Default")
      (node (ref "C2") (pin "1") (pinfunction "1_1") (pintype "passive"))
      (node (ref "R3") (pin "2") (pinfunction "2_2") (pintype "passive"))
      (node (ref "R4") (pin "1") (pinfunction "1_1") (pintype "passive"))
      (node (ref "U$14") (pin "92") (pinfunction "P42/IRQ10-DS/AN002_92") (pintype "bidirectional"))
    )
    (net (code "107") (name "VBAT3") (class "Default")
      (node (ref "C45") (pin "+") (pinfunction "+_+") (pintype "passive"))
      (node (ref "L5") (pin "2") (pinfunction "2_2") (pintype "passive"))
      (node (ref "R1") (pin "1") (pinfunction "1_1") (pintype "passive"))
      (node (ref "VBAT3") (pin "TP") (pinfunction "TP_TP") (pintype "input"))
      (node (ref "X2") (pin "7") (pinfunction "KL_7") (pintype "passive"))
      (node (ref "X2") (pin "8") (pinfunction "KL_8") (pintype "passive"))
    )
    (net (code "108") (name "VBAT3_AD") (class "Default")
      (node (ref "C1") (pin "1") (pinfunction "1_1") (pintype "passive"))
      (node (ref "R1") (pin "2") (pinfunction "2_2") (pintype "passive"))
      (node (ref "R2") (pin "1") (pinfunction "1_1") (pintype "passive"))
      (node (ref "U$14") (pin "91") (pinfunction "P43/IRQ11-DS/AN003_91") (pintype "bidirectional"))
    )
    (net (code "109") (name "VBUS") (class "Default")
      (node (ref "CN2") (pin "VBUS") (pinfunction "VBUS_VBUS") (pintype "power_in"))
      (node (ref "D2") (pin "A") (pinfunction "A_A") (pintype "passive"))
      (node (ref "R27") (pin "1") (pinfunction "1_1") (pintype "passive"))
      (node (ref "U$2") (pin "VBUS") (pinfunction "VBUS_VBUS") (pintype "bidirectional"))
    )
    (net (code "110") (name "VIN") (class "Default")
      (node (ref "C30") (pin "1") (pinfunction "1_1") (pintype "passive"))
      (node (ref "C33") (pin "1") (pinfunction "1_1") (pintype "passive"))
      (node (ref "C36") (pin "1") (pinfunction "1_1") (pintype "passive"))
      (node (ref "C39") (pin "1") (pinfunction "1_1") (pintype "passive"))
      (node (ref "D1") (pin "C") (pinfunction "C_C") (pintype "passive"))
      (node (ref "U$16") (pin "P$5A") (pinfunction "VIN_P$5A") (pintype "bidirectional"))
      (node (ref "U$16") (pin "P$5B") (pinfunction "VIN1_P$5B") (pintype "bidirectional"))
      (node (ref "U$16") (pin "P$5C") (pinfunction "VIN2_P$5C") (pintype "bidirectional"))
      (node (ref "U$16") (pin "P$5D") (pinfunction "VIN3_P$5D") (pintype "bidirectional"))
      (node (ref "U$16") (pin "P$5E") (pinfunction "VIN4_P$5E") (pintype "bidirectional"))
      (node (ref "U$16") (pin "P$5F") (pinfunction "VIN5_P$5F") (pintype "bidirectional"))
      (node (ref "U$17") (pin "P$5A") (pinfunction "VIN_P$5A") (pintype "bidirectional"))
      (node (ref "U$17") (pin "P$5B") (pinfunction "VIN1_P$5B") (pintype "bidirectional"))
      (node (ref "U$17") (pin "P$5C") (pinfunction "VIN2_P$5C") (pintype "bidirectional"))
      (node (ref "U$17") (pin "P$5D") (pinfunction "VIN3_P$5D") (pintype "bidirectional"))
      (node (ref "U$17") (pin "P$5E") (pinfunction "VIN4_P$5E") (pintype "bidirectional"))
      (node (ref "U$17") (pin "P$5F") (pinfunction "VIN5_P$5F") (pintype "bidirectional"))
      (node (ref "U$18") (pin "P$5A") (pinfunction "VIN_P$5A") (pintype "bidirectional"))
      (node (ref "U$18") (pin "P$5B") (pinfunction "VIN1_P$5B") (pintype "bidirectional"))
      (node (ref "U$18") (pin "P$5C") (pinfunction "VIN2_P$5C") (pintype "bidirectional"))
      (node (ref "U$18") (pin "P$5D") (pinfunction "VIN3_P$5D") (pintype "bidirectional"))
      (node (ref "U$18") (pin "P$5E") (pinfunction "VIN4_P$5E") (pintype "bidirectional"))
      (node (ref "U$18") (pin "P$5F") (pinfunction "VIN5_P$5F") (pintype "bidirectional"))
      (node (ref "U$19") (pin "P$5A") (pinfunction "VIN_P$5A") (pintype "bidirectional"))
      (node (ref "U$19") (pin "P$5B") (pinfunction "VIN1_P$5B") (pintype "bidirectional"))
      (node (ref "U$19") (pin "P$5C") (pinfunction "VIN2_P$5C") (pintype "bidirectional"))
      (node (ref "U$19") (pin "P$5D") (pinfunction "VIN3_P$5D") (pintype "bidirectional"))
      (node (ref "U$19") (pin "P$5E") (pinfunction "VIN4_P$5E") (pintype "bidirectional"))
      (node (ref "U$19") (pin "P$5F") (pinfunction "VIN5_P$5F") (pintype "bidirectional"))
    )
    (net (code "111") (name "VSW0") (class "Default")
      (node (ref "L2") (pin "1") (pinfunction "1_1") (pintype "passive"))
      (node (ref "TP8") (pin "TP") (pinfunction "TP_TP") (pintype "input"))
      (node (ref "U$16") (pin "P$4A") (pinfunction "VSW_P$4A") (pintype "bidirectional"))
      (node (ref "U$16") (pin "P$4B") (pinfunction "VSW1_P$4B") (pintype "bidirectional"))
      (node (ref "U$16") (pin "P$4C") (pinfunction "VSW2_P$4C") (pintype "bidirectional"))
      (node (ref "U$16") (pin "P$4D") (pinfunction "VSW3_P$4D") (pintype "bidirectional"))
      (node (ref "U$16") (pin "P$4E") (pinfunction "VSW4_P$4E") (pintype "bidirectional"))
      (node (ref "U$16") (pin "P$4F") (pinfunction "VSW5_P$4F") (pintype "bidirectional"))
    )
    (net (code "112") (name "VSW1") (class "Default")
      (node (ref "L3") (pin "1") (pinfunction "1_1") (pintype "passive"))
      (node (ref "TP5") (pin "TP") (pinfunction "TP_TP") (pintype "input"))
      (node (ref "U$17") (pin "P$4A") (pinfunction "VSW_P$4A") (pintype "bidirectional"))
      (node (ref "U$17") (pin "P$4B") (pinfunction "VSW1_P$4B") (pintype "bidirectional"))
      (node (ref "U$17") (pin "P$4C") (pinfunction "VSW2_P$4C") (pintype "bidirectional"))
      (node (ref "U$17") (pin "P$4D") (pinfunction "VSW3_P$4D") (pintype "bidirectional"))
      (node (ref "U$17") (pin "P$4E") (pinfunction "VSW4_P$4E") (pintype "bidirectional"))
      (node (ref "U$17") (pin "P$4F") (pinfunction "VSW5_P$4F") (pintype "bidirectional"))
    )
    (net (code "113") (name "VSW2") (class "Default")
      (node (ref "L4") (pin "1") (pinfunction "1_1") (pintype "passive"))
      (node (ref "TP10") (pin "TP") (pinfunction "TP_TP") (pintype "input"))
      (node (ref "U$18") (pin "P$4A") (pinfunction "VSW_P$4A") (pintype "bidirectional"))
      (node (ref "U$18") (pin "P$4B") (pinfunction "VSW1_P$4B") (pintype "bidirectional"))
      (node (ref "U$18") (pin "P$4C") (pinfunction "VSW2_P$4C") (pintype "bidirectional"))
      (node (ref "U$18") (pin "P$4D") (pinfunction "VSW3_P$4D") (pintype "bidirectional"))
      (node (ref "U$18") (pin "P$4E") (pinfunction "VSW4_P$4E") (pintype "bidirectional"))
      (node (ref "U$18") (pin "P$4F") (pinfunction "VSW5_P$4F") (pintype "bidirectional"))
    )
    (net (code "114") (name "VSW3") (class "Default")
      (node (ref "L5") (pin "1") (pinfunction "1_1") (pintype "passive"))
      (node (ref "TP15") (pin "TP") (pinfunction "TP_TP") (pintype "input"))
      (node (ref "U$19") (pin "P$4A") (pinfunction "VSW_P$4A") (pintype "bidirectional"))
      (node (ref "U$19") (pin "P$4B") (pinfunction "VSW1_P$4B") (pintype "bidirectional"))
      (node (ref "U$19") (pin "P$4C") (pinfunction "VSW2_P$4C") (pintype "bidirectional"))
      (node (ref "U$19") (pin "P$4D") (pinfunction "VSW3_P$4D") (pintype "bidirectional"))
      (node (ref "U$19") (pin "P$4E") (pinfunction "VSW4_P$4E") (pintype "bidirectional"))
      (node (ref "U$19") (pin "P$4F") (pinfunction "VSW5_P$4F") (pintype "bidirectional"))
    )
    (net (code "115") (name "XCIN") (class "Default")
      (node (ref "C9") (pin "2") (pinfunction "2_2") (pintype "passive"))
      (node (ref "Q1") (pin "1") (pinfunction "1_1") (pintype "passive"))
      (node (ref "U$14") (pin "8") (pinfunction "XCIN_8") (pintype "bidirectional"))
    )
    (net (code "116") (name "XCOUT") (class "Default")
      (node (ref "C11") (pin "2") (pinfunction "2_2") (pintype "passive"))
      (node (ref "Q1") (pin "4") (pinfunction "2_4") (pintype "passive"))
      (node (ref "U$14") (pin "9") (pinfunction "XCOUT_9") (pintype "bidirectional"))
    )
    (net (code "117") (name "XTAL") (class "Default")
      (node (ref "C6") (pin "2") (pinfunction "2_2") (pintype "passive"))
      (node (ref "U$14") (pin "11") (pinfunction "XTAL/P37_11") (pintype "bidirectional"))
      (node (ref "X1") (pin "P$1") (pinfunction "P$1_P$1") (pintype "bidirectional"))
    )
    (net (code "118") (name "unconnected-(CN2-PadID)") (class "Default")
      (node (ref "CN2") (pin "ID") (pinfunction "ID_ID") (pintype "bidirectional"))
    )
    (net (code "119") (name "unconnected-(JP2-Pad6)") (class "Default")
      (node (ref "JP2") (pin "6") (pinfunction "6_6") (pintype "passive"))
    )
    (net (code "120") (name "unconnected-(U$3-NC-PadP$3)") (class "Default")
      (node (ref "U$3") (pin "P$3") (pinfunction "NC_P$3") (pintype "bidirectional"))
    )
    (net (code "121") (name "unconnected-(U1-AUXCL-Pad7)") (class "Default")
      (node (ref "U1") (pin "7") (pinfunction "AUXCL_7") (pintype "bidirectional"))
    )
    (net (code "122") (name "unconnected-(U1-AUXDA-Pad6)") (class "Default")
      (node (ref "U1") (pin "6") (pinfunction "AUXDA_6") (pintype "bidirectional"))
    )
    (net (code "123") (name "unconnected-(U1-CLKOUT-Pad22)") (class "Default")
      (node (ref "U1") (pin "22") (pinfunction "CLKOUT_22") (pintype "bidirectional"))
    )
    (net (code "124") (name "unconnected-(U1-FSYNC-Pad11)") (class "Default")
      (node (ref "U1") (pin "11") (pinfunction "FSYNC_11") (pintype "bidirectional"))
    )
    (net (code "125") (name "unconnected-(U2-AUXCL-Pad7)") (class "Default")
      (node (ref "U2") (pin "7") (pinfunction "AUXCL_7") (pintype "bidirectional"))
    )
    (net (code "126") (name "unconnected-(U2-AUXDA-Pad6)") (class "Default")
      (node (ref "U2") (pin "6") (pinfunction "AUXDA_6") (pintype "bidirectional"))
    )
    (net (code "127") (name "unconnected-(U2-CLKOUT-Pad22)") (class "Default")
      (node (ref "U2") (pin "22") (pinfunction "CLKOUT_22") (pintype "bidirectional"))
    )
    (net (code "128") (name "unconnected-(U2-FSYNC-Pad11)") (class "Default")
      (node (ref "U2") (pin "11") (pinfunction "FSYNC_11") (pintype "bidirectional"))
    )
    (net (code "129") (name "~{OLED_CS}") (class "Default")
      (node (ref "JP2") (pin "10") (pinfunction "10_10") (pintype "passive"))
      (node (ref "U$14") (pin "39") (pinfunction "P55/~{WAIT}/CRX1/IRQ10_39") (pintype "bidirectional"))
      (node (ref "U$3") (pin "P$16") (pinfunction "~{CS}_P$16") (pintype "bidirectional"))
    )
    (net (code "130") (name "~{OLED_DC}") (class "Default")
      (node (ref "U$14") (pin "40") (pinfunction "P54/ALE/~{CTS2}/~{RTS2}/~{SS2}/CTX1_40") (pintype "bidirectional"))
      (node (ref "U$3") (pin "P$14") (pinfunction "~{DC}_P$14") (pintype "bidirectional"))
    )
    (net (code "131") (name "~{OLED_RD}") (class "Default")
      (node (ref "U$14") (pin "42") (pinfunction "P52/~{RD}/RXD2/SMISO2/SSCL2/SSLB3_42") (pintype "bidirectional"))
      (node (ref "U$3") (pin "P$12") (pinfunction "~{RD}_P$12") (pintype "bidirectional"))
    )
    (net (code "132") (name "~{OLED_RESET}") (class "Default")
      (node (ref "U$14") (pin "43") (pinfunction "P51/~{WR1}/~{BC1}/~{WAIT}/SCK2/SSLB2_43") (pintype "bidirectional"))
      (node (ref "U$3") (pin "P$15") (pinfunction "~{RESET}_P$15") (pintype "bidirectional"))
    )
    (net (code "133") (name "~{OLED_WR}") (class "Default")
      (node (ref "U$14") (pin "44") (pinfunction "P50/~{WR0}/~{WR}/TXD2/SMOSI2/SSDA2/SSLB1_44") (pintype "bidirectional"))
      (node (ref "U$3") (pin "P$13") (pinfunction "~{WR}_P$13") (pintype "bidirectional"))
    )
    (net (code "134") (name "~{RESET}") (class "Default")
      (node (ref "IC2") (pin "2") (pinfunction "~{RESET}_2") (pintype "input"))
      (node (ref "JP2") (pin "13") (pinfunction "13_13") (pintype "passive"))
      (node (ref "R22") (pin "2") (pinfunction "2_2") (pintype "passive"))
      (node (ref "S9") (pin "1") (pinfunction "1_1") (pintype "passive"))
      (node (ref "U$14") (pin "10") (pinfunction "~{RES}_10") (pintype "bidirectional"))
    )
    (net (code "135") (name "~{SKIP0}") (class "Default")
      (node (ref "U$14") (pin "69") (pinfunction "PA1/A1/SCK5/SSLA2/IRQ11_69") (pintype "bidirectional"))
      (node (ref "U$16") (pin "P$1") (pinfunction "~{SKIP}_P$1") (pintype "bidirectional"))
    )
    (net (code "136") (name "~{SKIP1}") (class "Default")
      (node (ref "U$14") (pin "68") (pinfunction "PA2/A2/PO18/RXD5/SMISO5/SSCL5/SSLA3_68") (pintype "bidirectional"))
      (node (ref "U$17") (pin "P$1") (pinfunction "~{SKIP}_P$1") (pintype "bidirectional"))
    )
    (net (code "137") (name "~{SKIP2}") (class "Default")
      (node (ref "U$14") (pin "67") (pinfunction "PA3/A3/RXD5/SMISO5/SSCL5/IRQ6-DS_67") (pintype "bidirectional"))
      (node (ref "U$18") (pin "P$1") (pinfunction "~{SKIP}_P$1") (pintype "bidirectional"))
    )
    (net (code "138") (name "~{SKIP3}") (class "Default")
      (node (ref "U$14") (pin "65") (pinfunction "PA5/A5/RSPCKA_65") (pintype "bidirectional"))
      (node (ref "U$19") (pin "P$1") (pinfunction "~{SKIP}_P$1") (pintype "bidirectional"))
    )
    (net (code "139") (name "~{SW1}") (class "Default")
      (node (ref "S6") (pin "3") (pinfunction "3_3") (pintype "passive"))
      (node (ref "S6") (pin "4") (pinfunction "4_4") (pintype "passive"))
      (node (ref "U$14") (pin "17") (pinfunction "P33/MTIOC0D/TIOCD0/TMRI3/PO11/RXD6/RXD0/SMISO6/SMISO0/SSCL6/SSCL0/IRQ3-DS_17") (pintype "bidirectional"))
    )
    (net (code "140") (name "~{SW2}") (class "Default")
      (node (ref "S7") (pin "3") (pinfunction "3_3") (pintype "passive"))
      (node (ref "S7") (pin "4") (pinfunction "4_4") (pintype "passive"))
      (node (ref "U$14") (pin "18") (pinfunction "P32/TXD6/TXD0/SMOSI6/SMOSI0/SSDA6/SSDA0/IRQ3-DS_18") (pintype "bidirectional"))
    )
    (net (code "141") (name "~{SW3}{slash}TMS") (class "Default")
      (node (ref "JP2") (pin "9") (pinfunction "9_9") (pintype "passive"))
      (node (ref "S8") (pin "3") (pinfunction "3_3") (pintype "passive"))
      (node (ref "S8") (pin "4") (pinfunction "4_4") (pintype "passive"))
      (node (ref "U$14") (pin "19") (pinfunction "~{CTS1}/~{RTS1}/~{SS1}/SSLB0/IRQ1-DS_19") (pintype "bidirectional"))
    )
    (net (code "142") (name "~{SW4}{slash}TDI") (class "Default")
      (node (ref "S2") (pin "3") (pinfunction "3_3") (pintype "passive"))
      (node (ref "S2") (pin "4") (pinfunction "4_4") (pintype "passive"))
      (node (ref "U$14") (pin "20") (pinfunction "P30/RXD1/SMISO1/SSCL1/MISOB/IRQ0-DS_20") (pintype "bidirectional"))
    )
    (net (code "143") (name "~{TRST}") (class "Default")
      (node (ref "JP2") (pin "3") (pinfunction "3_3") (pintype "passive"))
      (node (ref "U$14") (pin "16") (pinfunction "~{TRST}/P34/MTIOC0A/TMCI3/PO12/~{POE2}/SCK6/SCK0/IRQ4_16") (pintype "bidirectional"))
      (node (ref "X3") (pin "1") (pinfunction "S_1") (pintype "passive"))
    )
  )
)
